# motor_board_tmc.net
KiCad netlist of a schematic drawn in EAGLE
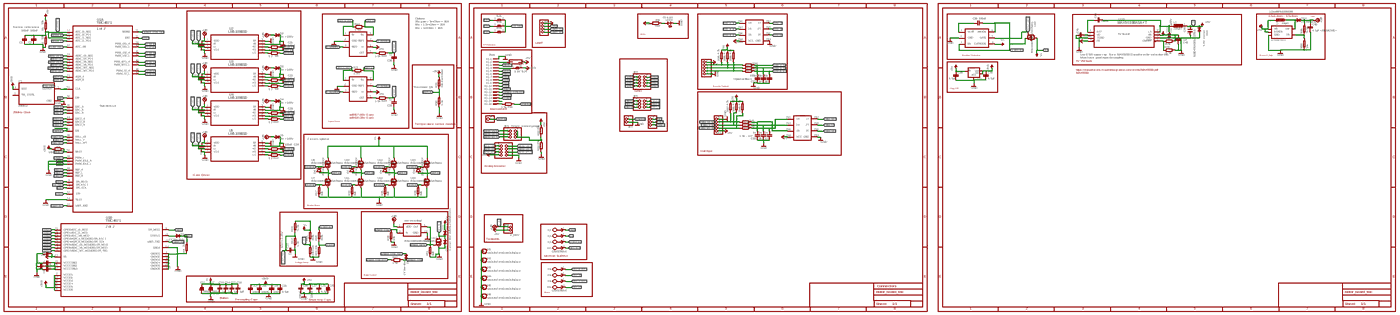
[diagram p0: schematic, sheet 1, overview]
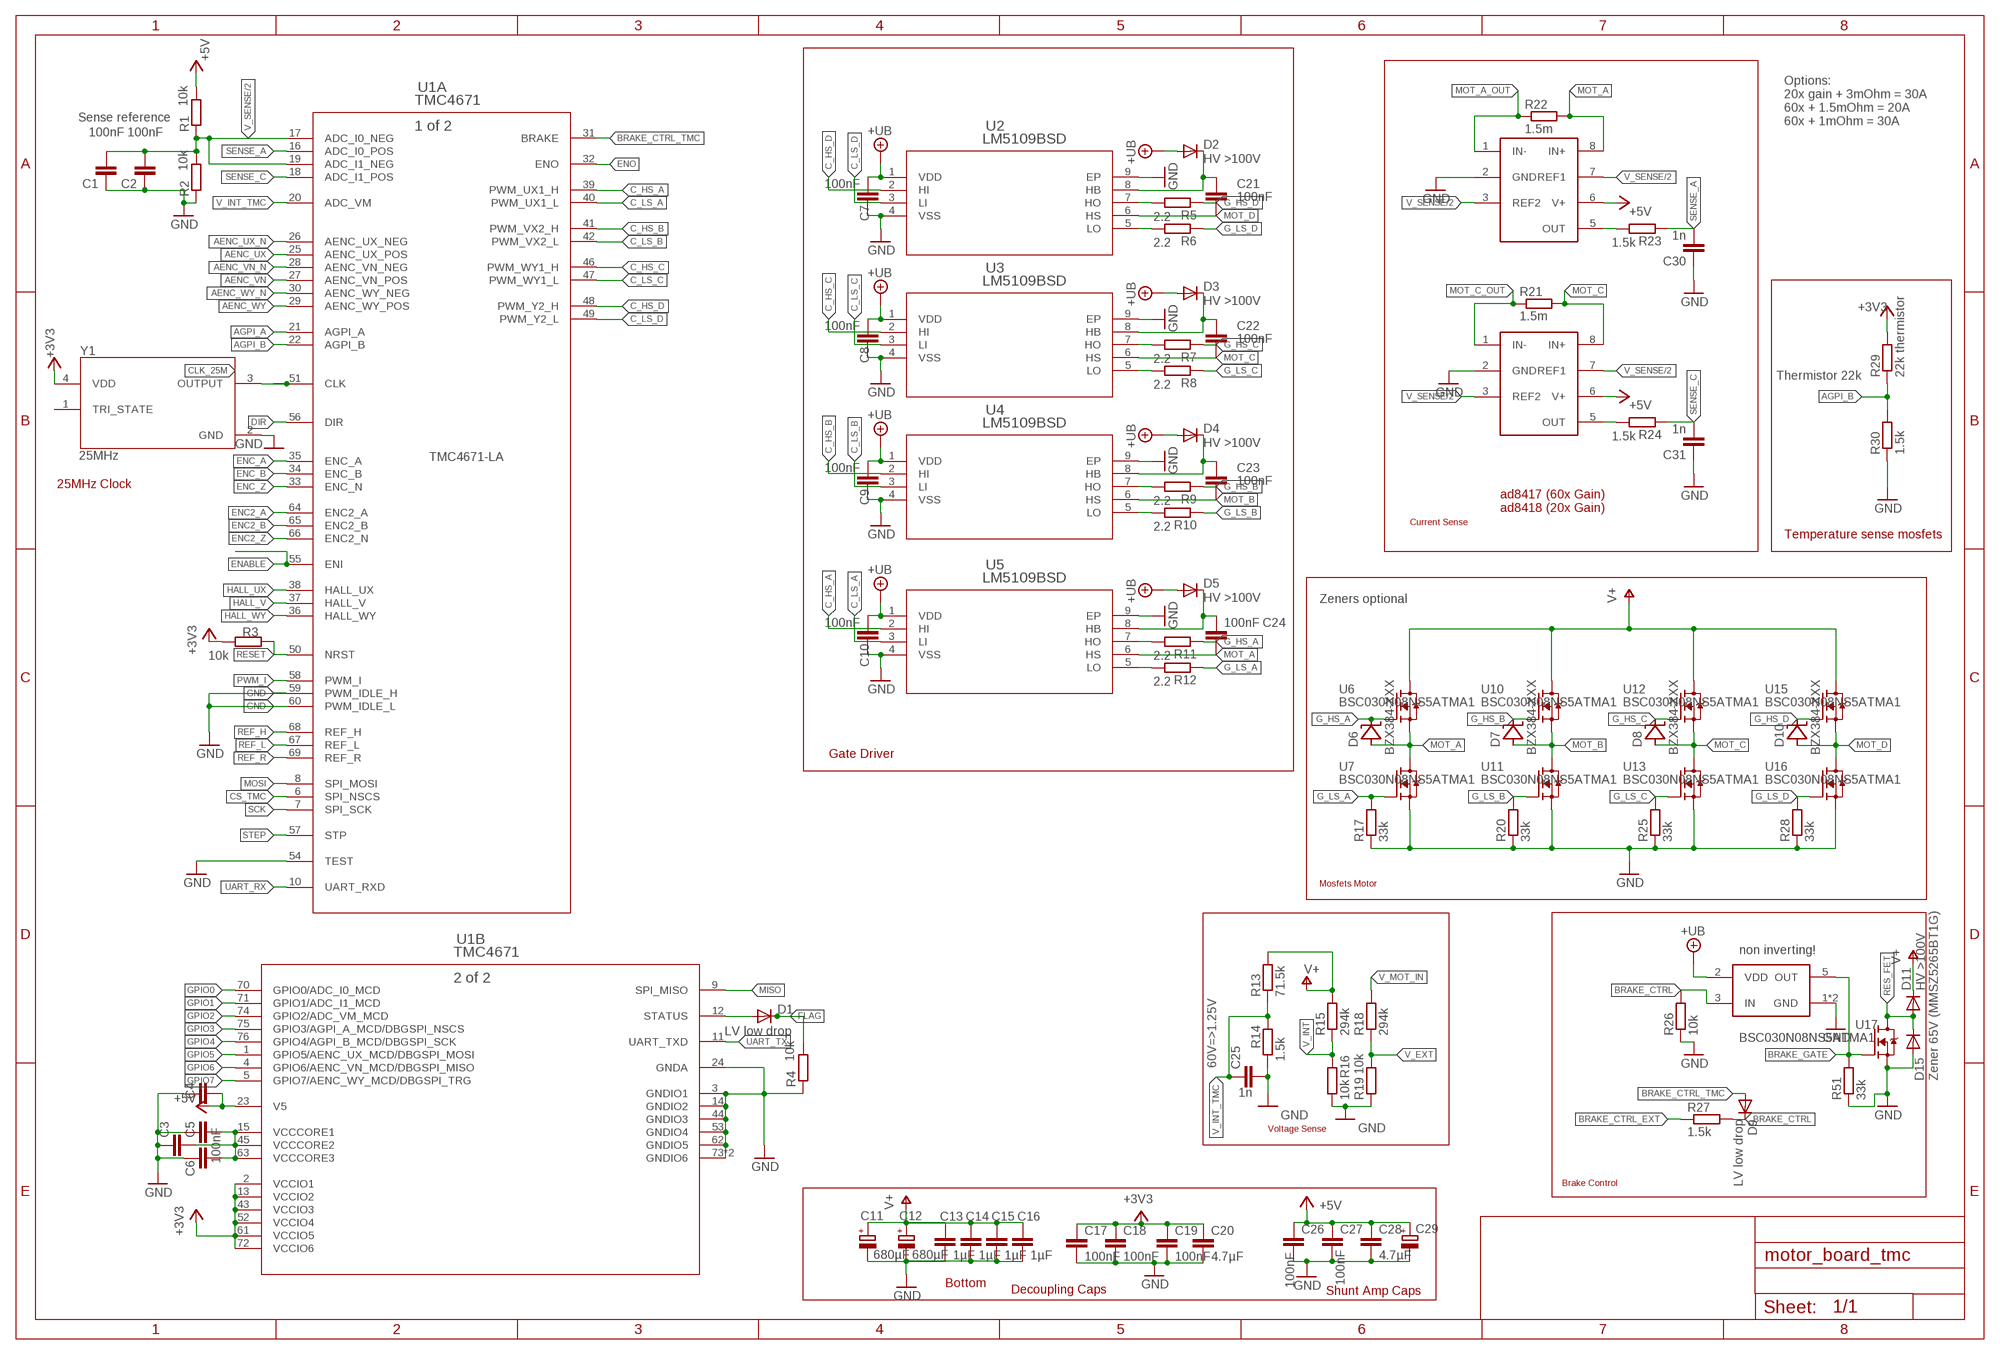
[diagram p1: schematic, sheet 1, part 1 of 4]
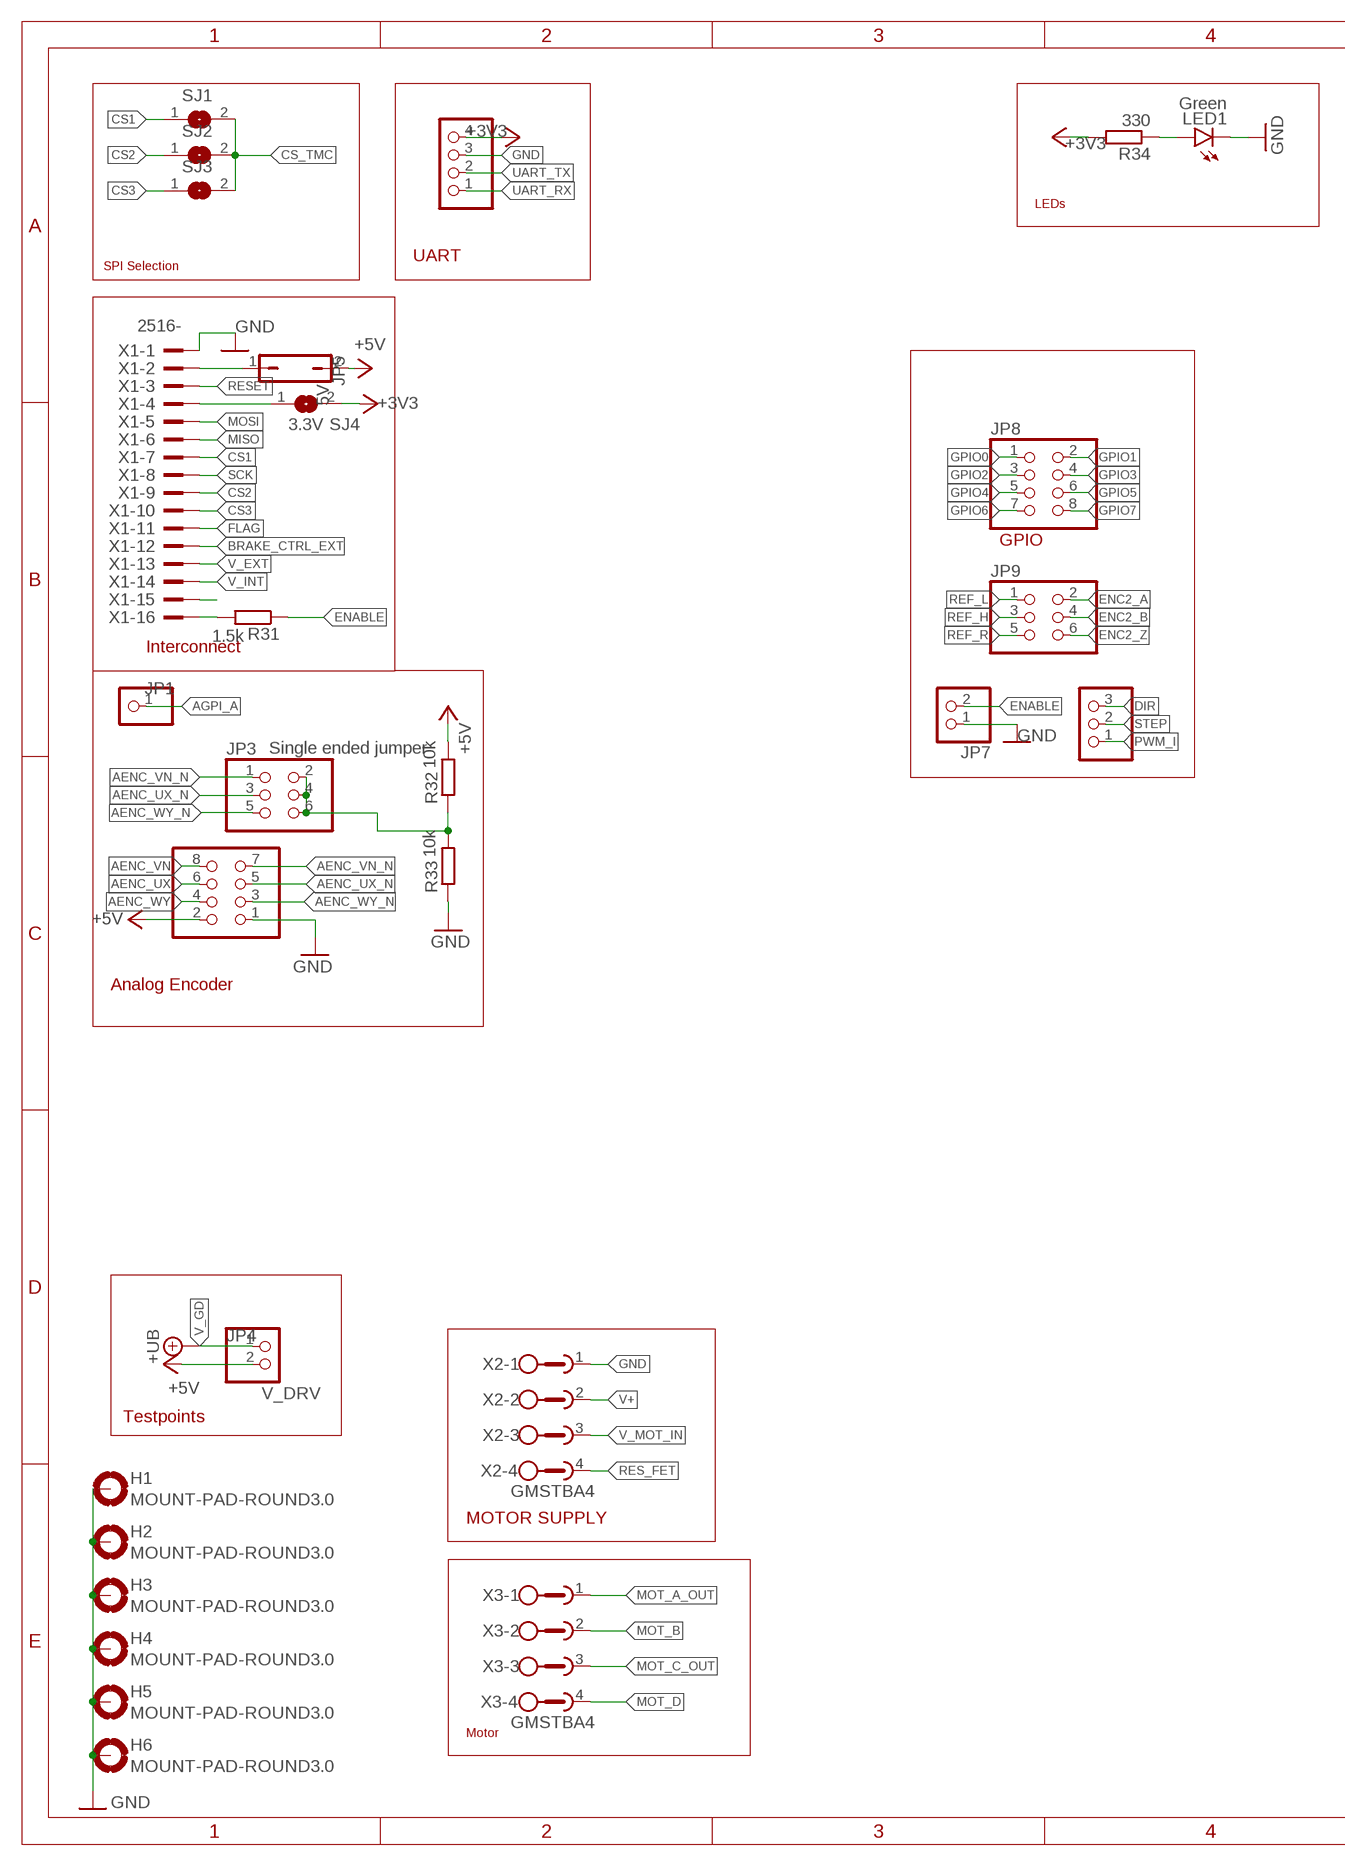
[diagram p2: schematic, sheet 1, part 2 of 4]
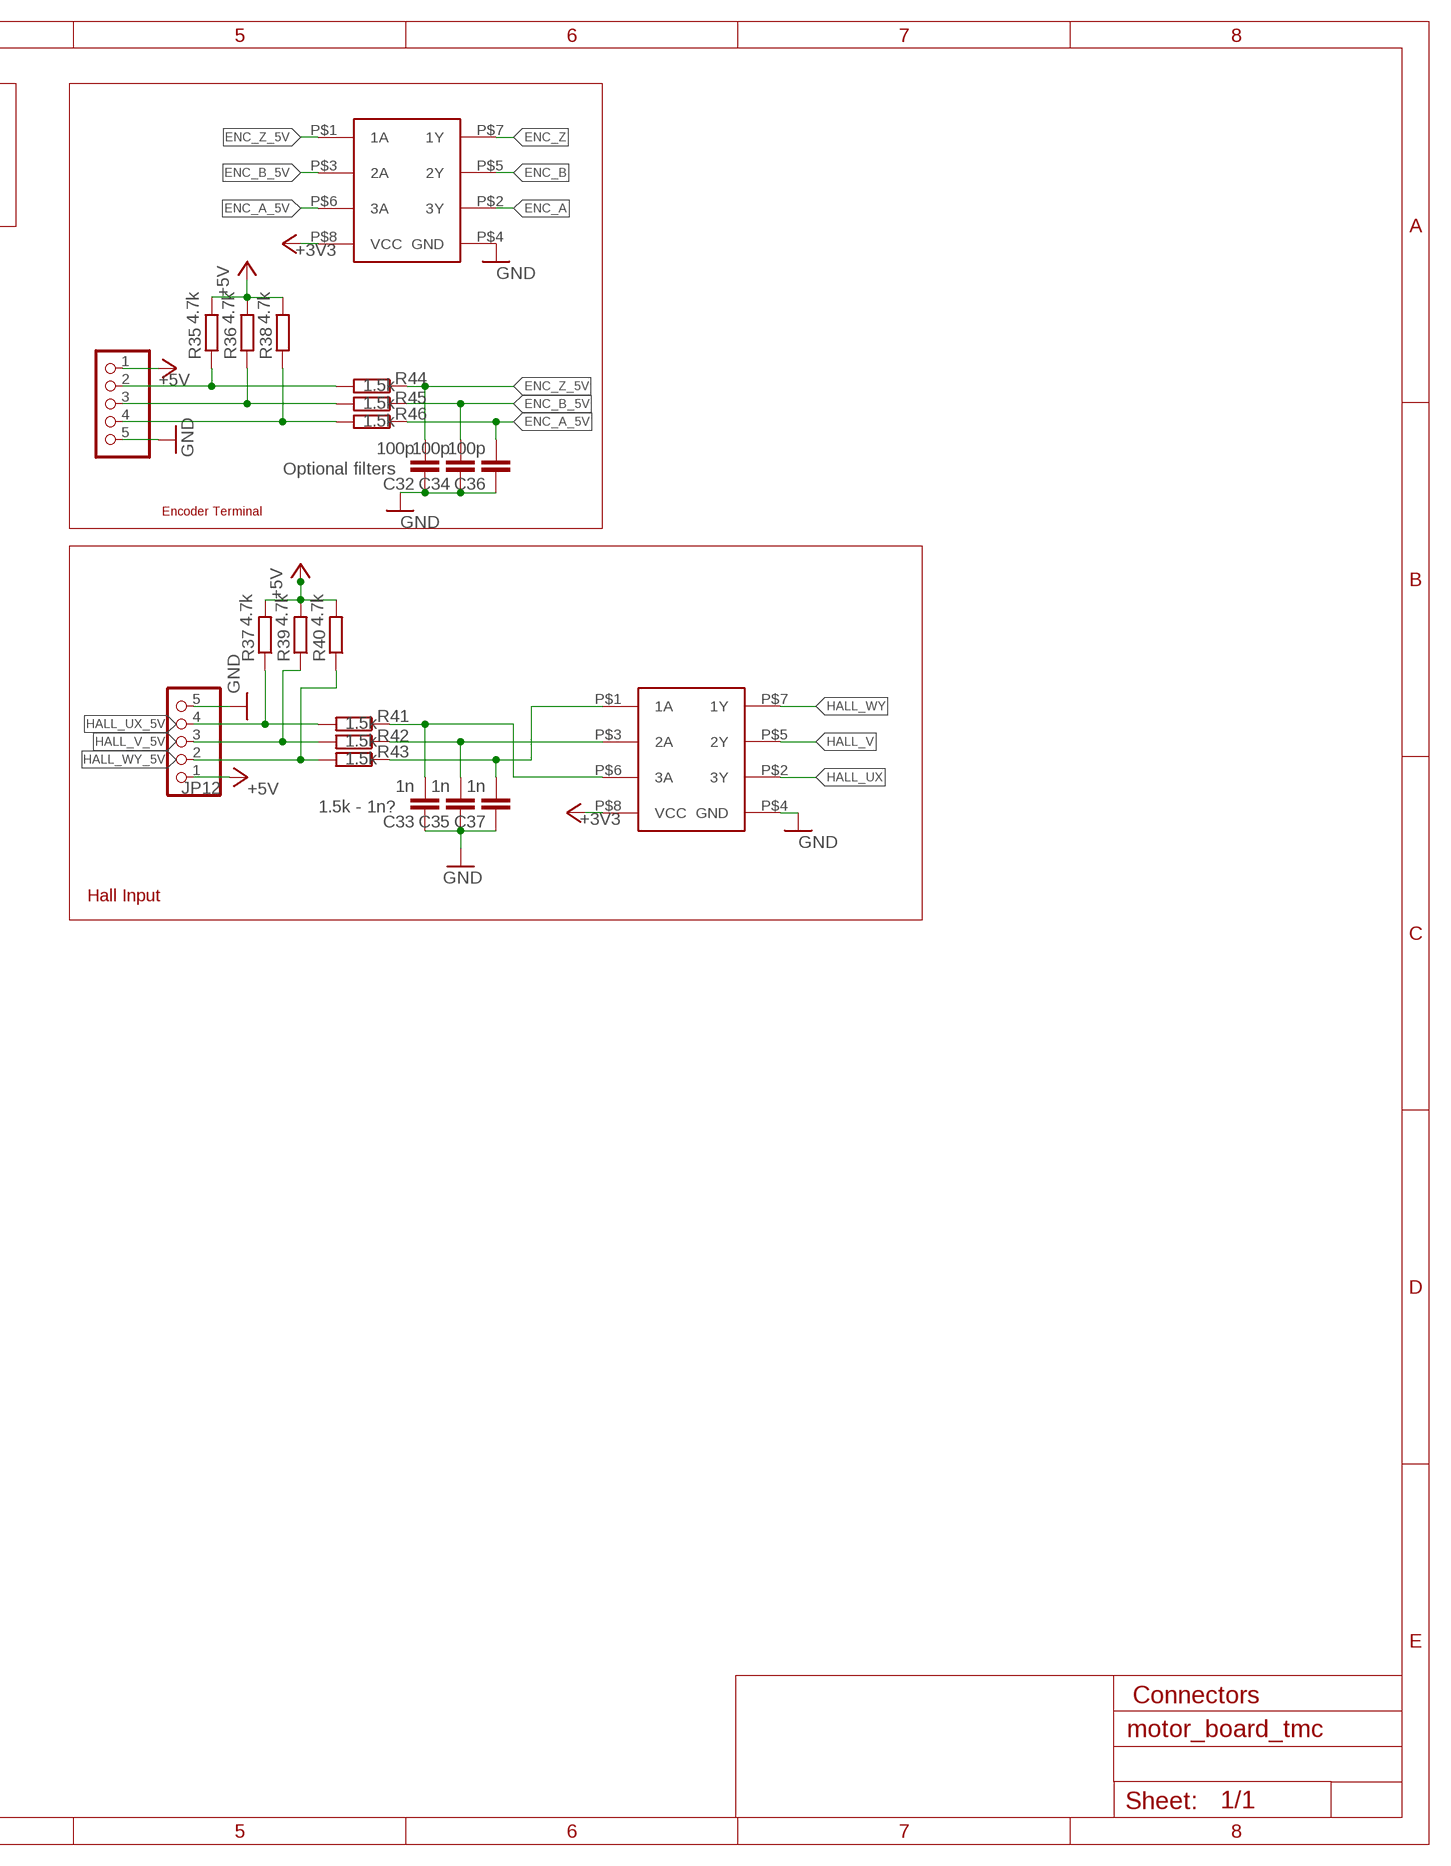
[diagram p3: schematic, sheet 1, part 3 of 4]
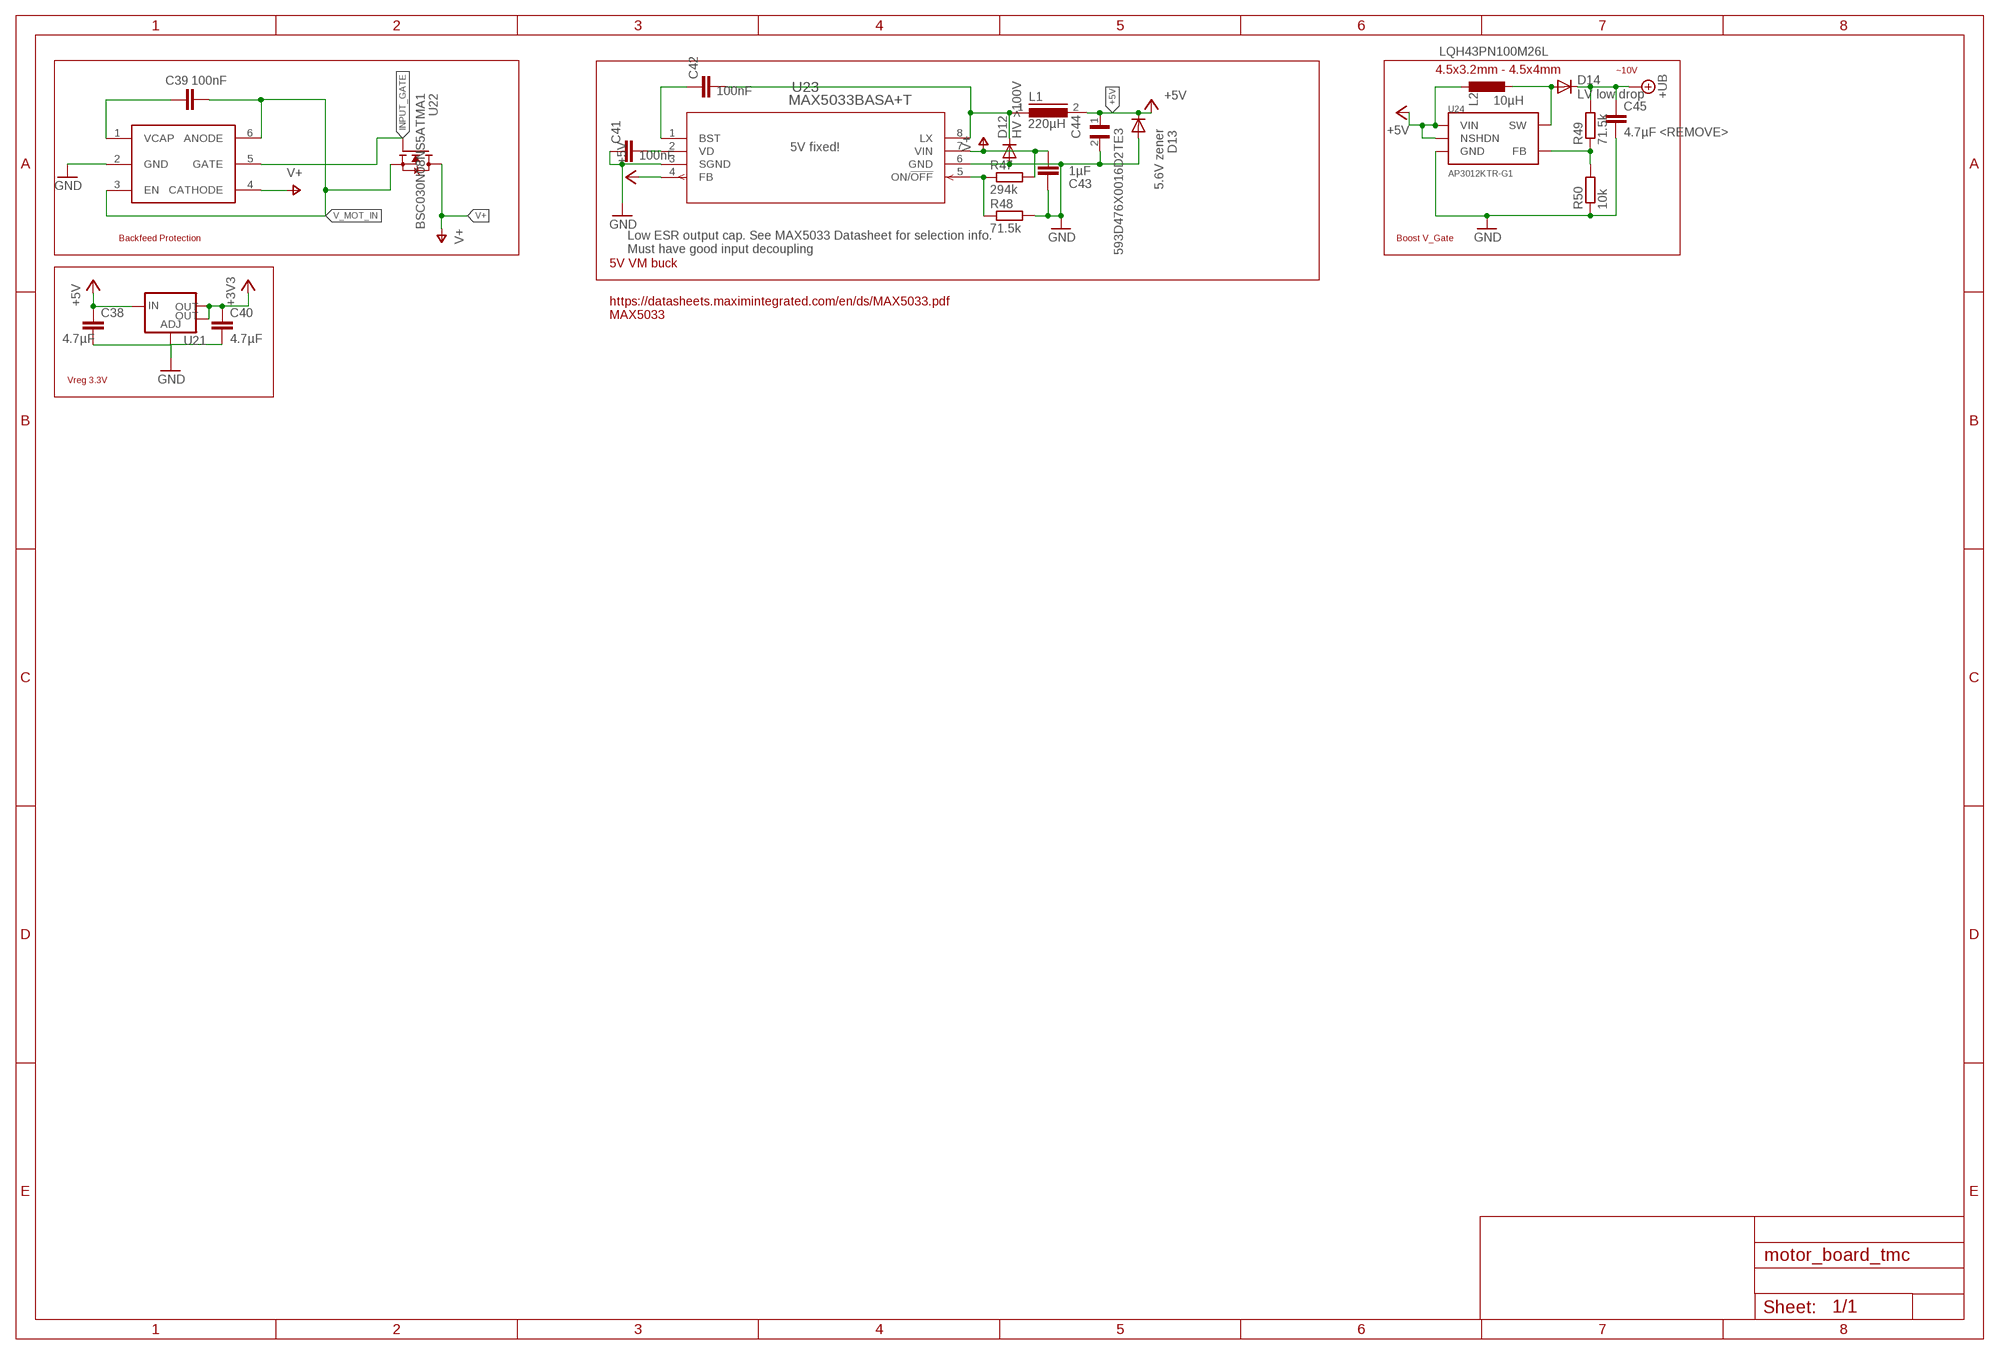
[diagram p4: schematic, sheet 1, part 4 of 4]

(export (version "E")
  (design (tool "Eeschema 10.0.6"))
  (components
    (comp (ref "C1")
      (value "100nF")
      (footprint "eagle-import:C0603")
      (libsource (lib "eagle-import") (part "C-EUC0603"))
    )
    (comp (ref "C2")
      (value "100nF")
      (footprint "eagle-import:C0603")
      (libsource (lib "eagle-import") (part "C-EUC0603"))
    )
    (comp (ref "C3")
      (value "100nF")
      (footprint "eagle-import:C0603")
      (libsource (lib "eagle-import") (part "C-EUC0603"))
    )
    (comp (ref "C4")
      (value "100nF")
      (footprint "eagle-import:C0603")
      (libsource (lib "eagle-import") (part "C-EUC0603"))
    )
    (comp (ref "C5")
      (value "100nF")
      (footprint "eagle-import:C0603")
      (libsource (lib "eagle-import") (part "C-EUC0603"))
    )
    (comp (ref "C6")
      (value "100nF")
      (footprint "eagle-import:C0603")
      (libsource (lib "eagle-import") (part "C-EUC0603"))
    )
    (comp (ref "C7")
      (value "100nF")
      (footprint "eagle-import:C0603")
      (libsource (lib "eagle-import") (part "C-EUC0603"))
    )
    (comp (ref "C8")
      (value "100nF")
      (footprint "eagle-import:C0603")
      (libsource (lib "eagle-import") (part "C-EUC0603"))
    )
    (comp (ref "C9")
      (value "100nF")
      (footprint "eagle-import:C0603")
      (libsource (lib "eagle-import") (part "C-EUC0603"))
    )
    (comp (ref "C10")
      (value "100nF")
      (footprint "eagle-import:C0603")
      (libsource (lib "eagle-import") (part "C-EUC0603"))
    )
    (comp (ref "C11")
      (value "680µF")
      (footprint "eagle-import:E7,5-16")
      (libsource (lib "eagle-import") (part "CPOL-EUE7.5-16"))
    )
    (comp (ref "C12")
      (value "680µF")
      (footprint "eagle-import:E7,5-16")
      (libsource (lib "eagle-import") (part "CPOL-EUE7.5-16"))
    )
    (comp (ref "C13")
      (value "1µF")
      (footprint "eagle-import:C1206")
      (libsource (lib "eagle-import") (part "C-EUC1206"))
    )
    (comp (ref "C14")
      (value "1µF")
      (footprint "eagle-import:C1206")
      (libsource (lib "eagle-import") (part "C-EUC1206"))
    )
    (comp (ref "C15")
      (value "1µF")
      (footprint "eagle-import:C1206")
      (libsource (lib "eagle-import") (part "C-EUC1206"))
    )
    (comp (ref "C16")
      (value "1µF")
      (footprint "eagle-import:C1206")
      (libsource (lib "eagle-import") (part "C-EUC1206"))
    )
    (comp (ref "C17")
      (value "100nF")
      (footprint "eagle-import:C0603")
      (libsource (lib "eagle-import") (part "C-EUC0603"))
    )
    (comp (ref "C18")
      (value "100nF")
      (footprint "eagle-import:C0603")
      (libsource (lib "eagle-import") (part "C-EUC0603"))
    )
    (comp (ref "C19")
      (value "100nF")
      (footprint "eagle-import:C0603")
      (libsource (lib "eagle-import") (part "C-EUC0603"))
    )
    (comp (ref "C20")
      (value "4.7µF")
      (footprint "eagle-import:C0805")
      (libsource (lib "eagle-import") (part "C-EUC0805"))
    )
    (comp (ref "C21")
      (value "100nF")
      (footprint "eagle-import:C0805")
      (libsource (lib "eagle-import") (part "C-EUC0805"))
    )
    (comp (ref "C22")
      (value "100nF")
      (footprint "eagle-import:C0805")
      (libsource (lib "eagle-import") (part "C-EUC0805"))
    )
    (comp (ref "C23")
      (value "100nF")
      (footprint "eagle-import:C0805")
      (libsource (lib "eagle-import") (part "C-EUC0805"))
    )
    (comp (ref "C24")
      (value "100nF")
      (footprint "eagle-import:C0805")
      (libsource (lib "eagle-import") (part "C-EUC0805"))
    )
    (comp (ref "C25")
      (value "1n")
      (footprint "eagle-import:C0603")
      (libsource (lib "eagle-import") (part "C-EUC0603"))
    )
    (comp (ref "C26")
      (value "100nF")
      (footprint "eagle-import:C0603")
      (libsource (lib "eagle-import") (part "C-EUC0603"))
    )
    (comp (ref "C27")
      (value "100nF")
      (footprint "eagle-import:C0603")
      (libsource (lib "eagle-import") (part "C-EUC0603"))
    )
    (comp (ref "C28")
      (value "4.7µF")
      (footprint "eagle-import:C0805")
      (libsource (lib "eagle-import") (part "C-EUC0805"))
    )
    (comp (ref "C29")
      (value "CPOL-EUE5-8.5")
      (footprint "eagle-import:E5-8,5")
      (libsource (lib "eagle-import") (part "CPOL-EUE5-8.5"))
    )
    (comp (ref "C30")
      (value "1n")
      (footprint "eagle-import:C0603")
      (libsource (lib "eagle-import") (part "C-EUC0603"))
    )
    (comp (ref "C31")
      (value "1n")
      (footprint "eagle-import:C0603")
      (libsource (lib "eagle-import") (part "C-EUC0603"))
    )
    (comp (ref "C32")
      (value "100p")
      (footprint "eagle-import:C0603")
      (libsource (lib "eagle-import") (part "C-EUC0603"))
    )
    (comp (ref "C33")
      (value "1n")
      (footprint "eagle-import:C0603")
      (libsource (lib "eagle-import") (part "C-EUC0603"))
    )
    (comp (ref "C34")
      (value "100p")
      (footprint "eagle-import:C0603")
      (libsource (lib "eagle-import") (part "C-EUC0603"))
    )
    (comp (ref "C35")
      (value "1n")
      (footprint "eagle-import:C0603")
      (libsource (lib "eagle-import") (part "C-EUC0603"))
    )
    (comp (ref "C36")
      (value "100p")
      (footprint "eagle-import:C0603")
      (libsource (lib "eagle-import") (part "C-EUC0603"))
    )
    (comp (ref "C37")
      (value "1n")
      (footprint "eagle-import:C0603")
      (libsource (lib "eagle-import") (part "C-EUC0603"))
    )
    (comp (ref "C38")
      (value "4.7µF")
      (footprint "eagle-import:C0805")
      (libsource (lib "eagle-import") (part "C-EUC0805"))
    )
    (comp (ref "C39")
      (value "100nF")
      (footprint "eagle-import:C0805")
      (libsource (lib "eagle-import") (part "C-EUC0805"))
    )
    (comp (ref "C40")
      (value "4.7µF")
      (footprint "eagle-import:C0805")
      (libsource (lib "eagle-import") (part "C-EUC0805"))
    )
    (comp (ref "C41")
      (value "100nF")
      (footprint "eagle-import:C0603")
      (libsource (lib "eagle-import") (part "C-EUC0603"))
    )
    (comp (ref "C42")
      (value "100nF")
      (footprint "eagle-import:C0603")
      (libsource (lib "eagle-import") (part "C-EUC0603"))
    )
    (comp (ref "C43")
      (value "1µF")
      (footprint "eagle-import:C1206")
      (libsource (lib "eagle-import") (part "C-EUC1206"))
    )
    (comp (ref "C44")
      (value "593D476X0016D2TE3")
      (footprint "eagle-import:CAPPM7343X310N")
      (fields (field (name "DIGI-KEY_PART_NUMBER") "718-2142-1-ND") (field (name "MF") "Vishay Sprague"))
      (libsource (lib "eagle-import") (part "593D476X0016D2TE3"))
    )
    (comp (ref "C45")
      (value "4.7µF <REMOVE>")
      (footprint "eagle-import:C0805")
      (libsource (lib "eagle-import") (part "C-EUC0805"))
    )
    (comp (ref "D1")
      (value "LV low drop")
      (footprint "eagle-import:SOD-123FL")
      (libsource (lib "eagle-import") (part "DIODE_SOD-123FL"))
    )
    (comp (ref "D2")
      (value "HV >100V")
      (footprint "eagle-import:SOD-123FL")
      (libsource (lib "eagle-import") (part "DIODE_SOD-123FL"))
    )
    (comp (ref "D3")
      (value "HV >100V")
      (footprint "eagle-import:SOD-123FL")
      (libsource (lib "eagle-import") (part "DIODE_SOD-123FL"))
    )
    (comp (ref "D4")
      (value "HV >100V")
      (footprint "eagle-import:SOD-123FL")
      (libsource (lib "eagle-import") (part "DIODE_SOD-123FL"))
    )
    (comp (ref "D5")
      (value "HV >100V")
      (footprint "eagle-import:SOD-123FL")
      (libsource (lib "eagle-import") (part "DIODE_SOD-123FL"))
    )
    (comp (ref "D6")
      (value "BZX384-XXX")
      (footprint "eagle-import:SOD323-R")
      (libsource (lib "eagle-import") (part "BZX384-XXX"))
    )
    (comp (ref "D7")
      (value "BZX384-XXX")
      (footprint "eagle-import:SOD323-R")
      (libsource (lib "eagle-import") (part "BZX384-XXX"))
    )
    (comp (ref "D8")
      (value "BZX384-XXX")
      (footprint "eagle-import:SOD323-R")
      (libsource (lib "eagle-import") (part "BZX384-XXX"))
    )
    (comp (ref "D9")
      (value "LV low drop")
      (footprint "eagle-import:SOD-123FL")
      (libsource (lib "eagle-import") (part "DIODE_SOD-123FL"))
    )
    (comp (ref "D10")
      (value "BZX384-XXX")
      (footprint "eagle-import:SOD323-R")
      (libsource (lib "eagle-import") (part "BZX384-XXX"))
    )
    (comp (ref "D11")
      (value "HV >100V")
      (footprint "eagle-import:SOD-123FL")
      (libsource (lib "eagle-import") (part "DIODE_SOD-123FL"))
    )
    (comp (ref "D12")
      (value "HV >100V")
      (footprint "eagle-import:SOD-123FL")
      (libsource (lib "eagle-import") (part "DIODE_SOD-123FL"))
    )
    (comp (ref "D13")
      (value "5.6V zener")
      (footprint "eagle-import:SOD-123FL")
      (libsource (lib "eagle-import") (part "DIODE_SOD-123FL"))
    )
    (comp (ref "D14")
      (value "LV low drop")
      (footprint "eagle-import:SOD-123FL")
      (libsource (lib "eagle-import") (part "DIODE_SOD-123FL"))
    )
    (comp (ref "D15")
      (value "Zener 65V (MMSZ5265BT1G)")
      (footprint "eagle-import:SOD-123FL")
      (libsource (lib "eagle-import") (part "DIODE_SOD-123FL"))
    )
    (comp (ref "H1")
      (value "MOUNT-PAD-ROUND3.0")
      (footprint "eagle-import:3,0-PAD")
      (libsource (lib "eagle-import") (part "MOUNT-PAD-ROUND3.0"))
    )
    (comp (ref "H2")
      (value "MOUNT-PAD-ROUND3.0")
      (footprint "eagle-import:3,0-PAD")
      (libsource (lib "eagle-import") (part "MOUNT-PAD-ROUND3.0"))
    )
    (comp (ref "H3")
      (value "MOUNT-PAD-ROUND3.0")
      (footprint "eagle-import:3,0-PAD")
      (libsource (lib "eagle-import") (part "MOUNT-PAD-ROUND3.0"))
    )
    (comp (ref "H4")
      (value "MOUNT-PAD-ROUND3.0")
      (footprint "eagle-import:3,0-PAD")
      (libsource (lib "eagle-import") (part "MOUNT-PAD-ROUND3.0"))
    )
    (comp (ref "H5")
      (value "MOUNT-PAD-ROUND3.0")
      (footprint "eagle-import:3,0-PAD")
      (libsource (lib "eagle-import") (part "MOUNT-PAD-ROUND3.0"))
    )
    (comp (ref "H6")
      (value "MOUNT-PAD-ROUND3.0")
      (footprint "eagle-import:3,0-PAD")
      (libsource (lib "eagle-import") (part "MOUNT-PAD-ROUND3.0"))
    )
    (comp (ref "JP1")
      (value "PINHD-1X1")
      (footprint "eagle-import:1X01")
      (libsource (lib "eagle-import") (part "PINHD-1X1"))
    )
    (comp (ref "JP2")
      (value "PINHD-2X4")
      (footprint "eagle-import:2X04")
      (libsource (lib "eagle-import") (part "PINHD-2X4"))
    )
    (comp (ref "JP3")
      (value "PINHD-2X3")
      (footprint "eagle-import:2X03")
      (libsource (lib "eagle-import") (part "PINHD-2X3"))
    )
    (comp (ref "JP4")
      (value "V_DRV")
      (footprint "eagle-import:1X02")
      (libsource (lib "eagle-import") (part "PINHD-1X2"))
    )
    (comp (ref "JP5")
      (value "5V")
      (footprint "eagle-import:JP1")
      (libsource (lib "eagle-import") (part "JP1Q"))
    )
    (comp (ref "JP6")
      (value "PINHD-1X4")
      (footprint "eagle-import:1X04")
      (libsource (lib "eagle-import") (part "PINHD-1X4"))
    )
    (comp (ref "JP7")
      (value "PINHD-1X2")
      (footprint "eagle-import:1X02")
      (libsource (lib "eagle-import") (part "PINHD-1X2"))
    )
    (comp (ref "JP8")
      (value "PINHD-2X4")
      (footprint "eagle-import:2X04")
      (libsource (lib "eagle-import") (part "PINHD-2X4"))
    )
    (comp (ref "JP9")
      (value "PINHD-2X3")
      (footprint "eagle-import:2X03")
      (libsource (lib "eagle-import") (part "PINHD-2X3"))
    )
    (comp (ref "JP10")
      (value "PINHD-1X3")
      (footprint "eagle-import:1X03")
      (libsource (lib "eagle-import") (part "PINHD-1X3"))
    )
    (comp (ref "JP11")
      (value "PINHD-1X5")
      (footprint "eagle-import:1X05")
      (libsource (lib "eagle-import") (part "PINHD-1X5"))
    )
    (comp (ref "JP12")
      (value "PINHD-1X5")
      (footprint "eagle-import:1X05")
      (libsource (lib "eagle-import") (part "PINHD-1X5"))
    )
    (comp (ref "L1")
      (value "220µH")
      (footprint "eagle-import:8MMINDUCTOR")
      (libsource (lib "eagle-import") (part "8MMINDUCTOR"))
    )
    (comp (ref "L2")
      (value "10µH")
      (footprint "eagle-import:L4532P")
      (libsource (lib "eagle-import") (part "L-EUL4532P"))
    )
    (comp (ref "LED1")
      (value "Green")
      (footprint "eagle-import:SML0805")
      (libsource (lib "eagle-import") (part "LEDSML0805"))
    )
    (comp (ref "R1")
      (value "10k")
      (footprint "eagle-import:R0603")
      (libsource (lib "eagle-import") (part "R-EU_R0603"))
    )
    (comp (ref "R2")
      (value "10k")
      (footprint "eagle-import:R0603")
      (libsource (lib "eagle-import") (part "R-EU_R0603"))
    )
    (comp (ref "R3")
      (value "10k")
      (footprint "eagle-import:R0603")
      (libsource (lib "eagle-import") (part "R-EU_R0603"))
    )
    (comp (ref "R4")
      (value "10k")
      (footprint "eagle-import:R0603")
      (libsource (lib "eagle-import") (part "R-EU_R0603"))
    )
    (comp (ref "R5")
      (value "2.2")
      (footprint "eagle-import:R0603")
      (libsource (lib "eagle-import") (part "R-EU_R0603"))
    )
    (comp (ref "R6")
      (value "2.2")
      (footprint "eagle-import:R0603")
      (libsource (lib "eagle-import") (part "R-EU_R0603"))
    )
    (comp (ref "R7")
      (value "2.2")
      (footprint "eagle-import:R0603")
      (libsource (lib "eagle-import") (part "R-EU_R0603"))
    )
    (comp (ref "R8")
      (value "2.2")
      (footprint "eagle-import:R0603")
      (libsource (lib "eagle-import") (part "R-EU_R0603"))
    )
    (comp (ref "R9")
      (value "2.2")
      (footprint "eagle-import:R0603")
      (libsource (lib "eagle-import") (part "R-EU_R0603"))
    )
    (comp (ref "R10")
      (value "2.2")
      (footprint "eagle-import:R0603")
      (libsource (lib "eagle-import") (part "R-EU_R0603"))
    )
    (comp (ref "R11")
      (value "2.2")
      (footprint "eagle-import:R0603")
      (libsource (lib "eagle-import") (part "R-EU_R0603"))
    )
    (comp (ref "R12")
      (value "2.2")
      (footprint "eagle-import:R0603")
      (libsource (lib "eagle-import") (part "R-EU_R0603"))
    )
    (comp (ref "R13")
      (value "71.5k")
      (footprint "eagle-import:R0805")
      (libsource (lib "eagle-import") (part "R-EU_R0805"))
    )
    (comp (ref "R14")
      (value "1.5k")
      (footprint "eagle-import:R0603")
      (libsource (lib "eagle-import") (part "R-EU_R0603"))
    )
    (comp (ref "R15")
      (value "294k")
      (footprint "eagle-import:R0805")
      (libsource (lib "eagle-import") (part "R-EU_R0805"))
    )
    (comp (ref "R16")
      (value "10k")
      (footprint "eagle-import:R0603")
      (libsource (lib "eagle-import") (part "R-EU_R0603"))
    )
    (comp (ref "R17")
      (value "33k")
      (footprint "eagle-import:R0603")
      (libsource (lib "eagle-import") (part "R-EU_R0603"))
    )
    (comp (ref "R18")
      (value "294k")
      (footprint "eagle-import:R0805")
      (libsource (lib "eagle-import") (part "R-EU_R0805"))
    )
    (comp (ref "R19")
      (value "10k")
      (footprint "eagle-import:R0603")
      (libsource (lib "eagle-import") (part "R-EU_R0603"))
    )
    (comp (ref "R20")
      (value "33k")
      (footprint "eagle-import:R0603")
      (libsource (lib "eagle-import") (part "R-EU_R0603"))
    )
    (comp (ref "R21")
      (value "1.5m")
      (footprint "eagle-import:R2512")
      (libsource (lib "eagle-import") (part "R-EU_R2512"))
    )
    (comp (ref "R22")
      (value "1.5m")
      (footprint "eagle-import:R2512")
      (libsource (lib "eagle-import") (part "R-EU_R2512"))
    )
    (comp (ref "R23")
      (value "1.5k")
      (footprint "eagle-import:R0603")
      (libsource (lib "eagle-import") (part "R-EU_R0603"))
    )
    (comp (ref "R24")
      (value "1.5k")
      (footprint "eagle-import:R0603")
      (libsource (lib "eagle-import") (part "R-EU_R0603"))
    )
    (comp (ref "R25")
      (value "33k")
      (footprint "eagle-import:R0603")
      (libsource (lib "eagle-import") (part "R-EU_R0603"))
    )
    (comp (ref "R26")
      (value "10k")
      (footprint "eagle-import:R0603")
      (libsource (lib "eagle-import") (part "R-EU_R0603"))
    )
    (comp (ref "R27")
      (value "1.5k")
      (footprint "eagle-import:R0603")
      (libsource (lib "eagle-import") (part "R-EU_R0603"))
    )
    (comp (ref "R28")
      (value "33k")
      (footprint "eagle-import:R0603")
      (libsource (lib "eagle-import") (part "R-EU_R0603"))
    )
    (comp (ref "R29")
      (value "22k thermistor")
      (footprint "eagle-import:R0603")
      (libsource (lib "eagle-import") (part "R-EU_R0603"))
    )
    (comp (ref "R30")
      (value "1.5k")
      (footprint "eagle-import:R0603")
      (libsource (lib "eagle-import") (part "R-EU_R0603"))
    )
    (comp (ref "R31")
      (value "1.5k")
      (footprint "eagle-import:R0603")
      (libsource (lib "eagle-import") (part "R-EU_R0603"))
    )
    (comp (ref "R32")
      (value "10k")
      (footprint "eagle-import:R0603")
      (libsource (lib "eagle-import") (part "R-EU_R0603"))
    )
    (comp (ref "R33")
      (value "10k")
      (footprint "eagle-import:R0603")
      (libsource (lib "eagle-import") (part "R-EU_R0603"))
    )
    (comp (ref "R34")
      (value "330")
      (footprint "eagle-import:R0603")
      (libsource (lib "eagle-import") (part "R-EU_R0603"))
    )
    (comp (ref "R35")
      (value "4.7k")
      (footprint "eagle-import:R0603")
      (libsource (lib "eagle-import") (part "R-EU_R0603"))
    )
    (comp (ref "R36")
      (value "4.7k")
      (footprint "eagle-import:R0603")
      (libsource (lib "eagle-import") (part "R-EU_R0603"))
    )
    (comp (ref "R37")
      (value "4.7k")
      (footprint "eagle-import:R0603")
      (libsource (lib "eagle-import") (part "R-EU_R0603"))
    )
    (comp (ref "R38")
      (value "4.7k")
      (footprint "eagle-import:R0603")
      (libsource (lib "eagle-import") (part "R-EU_R0603"))
    )
    (comp (ref "R39")
      (value "4.7k")
      (footprint "eagle-import:R0603")
      (libsource (lib "eagle-import") (part "R-EU_R0603"))
    )
    (comp (ref "R40")
      (value "4.7k")
      (footprint "eagle-import:R0603")
      (libsource (lib "eagle-import") (part "R-EU_R0603"))
    )
    (comp (ref "R41")
      (value "1.5k")
      (footprint "eagle-import:R0603")
      (libsource (lib "eagle-import") (part "R-EU_R0603"))
    )
    (comp (ref "R42")
      (value "1.5k")
      (footprint "eagle-import:R0603")
      (libsource (lib "eagle-import") (part "R-EU_R0603"))
    )
    (comp (ref "R43")
      (value "1.5k")
      (footprint "eagle-import:R0603")
      (libsource (lib "eagle-import") (part "R-EU_R0603"))
    )
    (comp (ref "R44")
      (value "1.5k")
      (footprint "eagle-import:R0603")
      (libsource (lib "eagle-import") (part "R-EU_R0603"))
    )
    (comp (ref "R45")
      (value "1.5k")
      (footprint "eagle-import:R0603")
      (libsource (lib "eagle-import") (part "R-EU_R0603"))
    )
    (comp (ref "R46")
      (value "1.5k")
      (footprint "eagle-import:R0603")
      (libsource (lib "eagle-import") (part "R-EU_R0603"))
    )
    (comp (ref "R47")
      (value "294k")
      (footprint "eagle-import:R0805")
      (libsource (lib "eagle-import") (part "R-EU_R0805"))
    )
    (comp (ref "R48")
      (value "71.5k")
      (footprint "eagle-import:R0805")
      (libsource (lib "eagle-import") (part "R-EU_R0805"))
    )
    (comp (ref "R49")
      (value "71.5k")
      (footprint "eagle-import:R0805")
      (libsource (lib "eagle-import") (part "R-EU_R0805"))
    )
    (comp (ref "R50")
      (value "10k")
      (footprint "eagle-import:R0603")
      (libsource (lib "eagle-import") (part "R-EU_R0603"))
    )
    (comp (ref "R51")
      (value "33k")
      (footprint "eagle-import:R0603")
      (libsource (lib "eagle-import") (part "R-EU_R0603"))
    )
    (comp (ref "SJ1") (value "SJ") (footprint "eagle-import:SJ") (libsource (lib "eagle-import") (part "SJ")))
    (comp (ref "SJ2") (value "SJ") (footprint "eagle-import:SJ") (libsource (lib "eagle-import") (part "SJ")))
    (comp (ref "SJ3") (value "SJ") (footprint "eagle-import:SJ") (libsource (lib "eagle-import") (part "SJ")))
    (comp (ref "SJ4")
      (value "3.3V")
      (footprint "eagle-import:SJ")
      (libsource (lib "eagle-import") (part "SJ"))
    )
    (comp (ref "U1")
      (value "TMC4671")
      (footprint "eagle-import:QFN76_10P5X6P5")
      (fields (field (name "MANUFACTURER_PART_NUMBER") "TMC4671ES"))
      (libsource (lib "eagle-import") (part "TMC4671"))
    )
    (comp (ref "U2")
      (value "LM5109BSD")
      (footprint "eagle-import:SDC08A")
      (fields (field (name "MANUFACTURER_PART_NUMBER") "lm5109bsd"))
      (libsource (lib "eagle-import") (part "LM5109BSD"))
    )
    (comp (ref "U3")
      (value "LM5109BSD")
      (footprint "eagle-import:SDC08A")
      (fields (field (name "MANUFACTURER_PART_NUMBER") "lm5109bsd"))
      (libsource (lib "eagle-import") (part "LM5109BSD"))
    )
    (comp (ref "U4")
      (value "LM5109BSD")
      (footprint "eagle-import:SDC08A")
      (fields (field (name "MANUFACTURER_PART_NUMBER") "lm5109bsd"))
      (libsource (lib "eagle-import") (part "LM5109BSD"))
    )
    (comp (ref "U5")
      (value "LM5109BSD")
      (footprint "eagle-import:SDC08A")
      (fields (field (name "MANUFACTURER_PART_NUMBER") "lm5109bsd"))
      (libsource (lib "eagle-import") (part "LM5109BSD"))
    )
    (comp (ref "U6")
      (value "BSC030N08NS5ATMA1")
      (footprint "eagle-import:MOSFET_BSC093N04LSGATMA1")
      (fields (field (name "MF") "Infineon Technologies"))
      (libsource (lib "eagle-import") (part "BSC030N08NS5ATMA1"))
    )
    (comp (ref "U7")
      (value "BSC030N08NS5ATMA1")
      (footprint "eagle-import:MOSFET_BSC093N04LSGATMA1")
      (fields (field (name "MF") "Infineon Technologies"))
      (libsource (lib "eagle-import") (part "BSC030N08NS5ATMA1"))
    )
    (comp (ref "U8")
      (value "AD841X")
      (footprint "eagle-import:MSOP8")
      (libsource (lib "eagle-import") (part "AD841X"))
    )
    (comp (ref "U9")
      (value "AD841X")
      (footprint "eagle-import:MSOP8")
      (libsource (lib "eagle-import") (part "AD841X"))
    )
    (comp (ref "U10")
      (value "BSC030N08NS5ATMA1")
      (footprint "eagle-import:MOSFET_BSC093N04LSGATMA1")
      (fields (field (name "MF") "Infineon Technologies"))
      (libsource (lib "eagle-import") (part "BSC030N08NS5ATMA1"))
    )
    (comp (ref "U11")
      (value "BSC030N08NS5ATMA1")
      (footprint "eagle-import:MOSFET_BSC093N04LSGATMA1")
      (fields (field (name "MF") "Infineon Technologies"))
      (libsource (lib "eagle-import") (part "BSC030N08NS5ATMA1"))
    )
    (comp (ref "U12")
      (value "BSC030N08NS5ATMA1")
      (footprint "eagle-import:MOSFET_BSC093N04LSGATMA1")
      (fields (field (name "MF") "Infineon Technologies"))
      (libsource (lib "eagle-import") (part "BSC030N08NS5ATMA1"))
    )
    (comp (ref "U13")
      (value "BSC030N08NS5ATMA1")
      (footprint "eagle-import:MOSFET_BSC093N04LSGATMA1")
      (fields (field (name "MF") "Infineon Technologies"))
      (libsource (lib "eagle-import") (part "BSC030N08NS5ATMA1"))
    )
    (comp (ref "U14")
      (value "MCP14XX")
      (footprint "eagle-import:SOT23-5L")
      (libsource (lib "eagle-import") (part "MCP14XX"))
    )
    (comp (ref "U15")
      (value "BSC030N08NS5ATMA1")
      (footprint "eagle-import:MOSFET_BSC093N04LSGATMA1")
      (fields (field (name "MF") "Infineon Technologies"))
      (libsource (lib "eagle-import") (part "BSC030N08NS5ATMA1"))
    )
    (comp (ref "U16")
      (value "BSC030N08NS5ATMA1")
      (footprint "eagle-import:MOSFET_BSC093N04LSGATMA1")
      (fields (field (name "MF") "Infineon Technologies"))
      (libsource (lib "eagle-import") (part "BSC030N08NS5ATMA1"))
    )
    (comp (ref "U17")
      (value "BSC030N08NS5ATMA1")
      (footprint "eagle-import:MOSFET_BSC093N04LSGATMA1")
      (fields (field (name "MF") "Infineon Technologies"))
      (libsource (lib "eagle-import") (part "BSC030N08NS5ATMA1"))
    )
    (comp (ref "U18")
      (value "NC7NZ17K8X-3-BUFFER")
      (footprint "eagle-import:VFSOP-8")
      (libsource (lib "eagle-import") (part "NC7NZ17K8X-3-BUFFER"))
    )
    (comp (ref "U19")
      (value "NC7NZ17K8X-3-BUFFER")
      (footprint "eagle-import:VFSOP-8")
      (libsource (lib "eagle-import") (part "NC7NZ17K8X-3-BUFFER"))
    )
    (comp (ref "U20")
      (value "LM74700-Q1")
      (footprint "eagle-import:SOT23-6")
      (libsource (lib "eagle-import") (part "LM74700-Q1"))
    )
    (comp (ref "U21")
      (value "V_REG_LM1117SOT223")
      (footprint "eagle-import:SOT223")
      (libsource (lib "eagle-import") (part "V_REG_LM1117SOT223"))
    )
    (comp (ref "U22")
      (value "BSC030N08NS5ATMA1")
      (footprint "eagle-import:MOSFET_BSC093N04LSGATMA1")
      (fields (field (name "MF") "Infineon Technologies"))
      (libsource (lib "eagle-import") (part "BSC030N08NS5ATMA1"))
    )
    (comp (ref "U23")
      (value "MAX5033BASA+T")
      (footprint "eagle-import:21-0041B_8_MXM")
      (fields (field (name "MANUFACTURER_PART_NUMBER") "max5033basa+T"))
      (libsource (lib "eagle-import") (part "MAX5033BASA+T"))
    )
    (comp (ref "U24")
      (value "AP3012KTR-G1")
      (footprint "eagle-import:SOT23-5L")
      (libsource (lib "eagle-import") (part "AP3012KTR-G1"))
    )
    (comp (ref "X1")
      (value "2516-")
      (footprint "eagle-import:PAK100_2500-16")
      (libsource (lib "eagle-import") (part "2516-"))
    )
    (comp (ref "X2")
      (value "GMSTBA4")
      (footprint "eagle-import:GMSTBA4")
      (fields (field (name "MF") "FARNELL") (field (name "MPN") "1757268"))
      (libsource (lib "eagle-import") (part "GMSTBA4"))
    )
    (comp (ref "X3")
      (value "GMSTBA4")
      (footprint "eagle-import:GMSTBA4")
      (fields (field (name "MF") "FARNELL") (field (name "MPN") "1757268"))
      (libsource (lib "eagle-import") (part "GMSTBA4"))
    )
    (comp (ref "Y1")
      (value "25MHz")
      (footprint "eagle-import:ECS-327KE-TR")
      (fields
        (field (name "DIGIKEY_PART_NUMBER") "XC1751TR-ND")
        (field (name "MANUFACTURER") "ECS Inc.")
        (field (name "MPN") "ECS-327KE-TR")
        (field (name "CREATED_BY") "PCBLayout.com")
      )
      (libsource (lib "eagle-import") (part "ECS-327KE-TR"))
    )
  )
  (nets
    (net (code "1") (name "+3V3") (class "Default")
      (node (ref "C17") (pin "1") (pinfunction "1_1") (pintype "passive"))
      (node (ref "C18") (pin "1") (pinfunction "1_1") (pintype "passive"))
      (node (ref "C19") (pin "1") (pinfunction "1_1") (pintype "passive"))
      (node (ref "C20") (pin "1") (pinfunction "1_1") (pintype "passive"))
      (node (ref "C40") (pin "1") (pinfunction "1_1") (pintype "passive"))
      (node (ref "JP6") (pin "4") (pinfunction "4_4") (pintype "passive"))
      (node (ref "R29") (pin "2") (pinfunction "2_2") (pintype "passive"))
      (node (ref "R3") (pin "2") (pinfunction "2_2") (pintype "passive"))
      (node (ref "R34") (pin "2") (pinfunction "2_2") (pintype "passive"))
      (node (ref "SJ4") (pin "2") (pinfunction "2_2") (pintype "passive"))
      (node (ref "U1") (pin "13") (pinfunction "VCCIO2_13") (pintype "power_in"))
      (node (ref "U1") (pin "2") (pinfunction "VCCIO1_2") (pintype "power_in"))
      (node (ref "U1") (pin "43") (pinfunction "VCCIO3_43") (pintype "power_in"))
      (node (ref "U1") (pin "52") (pinfunction "VCCIO4_52") (pintype "power_in"))
      (node (ref "U1") (pin "61") (pinfunction "VCCIO5_61") (pintype "power_in"))
      (node (ref "U1") (pin "72") (pinfunction "VCCIO6_72") (pintype "power_in"))
      (node (ref "U18") (pin "P$8") (pinfunction "VCC_P$8") (pintype "bidirectional"))
      (node (ref "U19") (pin "P$8") (pinfunction "VCC_P$8") (pintype "bidirectional"))
      (node (ref "U21") (pin "2") (pinfunction "OUT_2") (pintype "output"))
      (node (ref "U21") (pin "4") (pinfunction "OUT_4") (pintype "output"))
      (node (ref "Y1") (pin "4") (pinfunction "VDD_4") (pintype "power_in"))
    )
    (net (code "2") (name "+5V") (class "Default")
      (node (ref "C26") (pin "1") (pinfunction "1_1") (pintype "passive"))
      (node (ref "C27") (pin "1") (pinfunction "1_1") (pintype "passive"))
      (node (ref "C28") (pin "1") (pinfunction "1_1") (pintype "passive"))
      (node (ref "C29") (pin "+") (pinfunction "+_+") (pintype "passive"))
      (node (ref "C38") (pin "1") (pinfunction "1_1") (pintype "passive"))
      (node (ref "C4") (pin "2") (pinfunction "2_2") (pintype "passive"))
      (node (ref "C44") (pin "1") (pinfunction "1_1") (pintype "passive"))
      (node (ref "D13") (pin "C") (pinfunction "C_C") (pintype "passive"))
      (node (ref "JP11") (pin "1") (pinfunction "1_1") (pintype "passive"))
      (node (ref "JP12") (pin "1") (pinfunction "1_1") (pintype "passive"))
      (node (ref "JP2") (pin "2") (pinfunction "2_2") (pintype "passive"))
      (node (ref "JP4") (pin "2") (pinfunction "2_2") (pintype "passive"))
      (node (ref "JP5") (pin "2") (pinfunction "2_2") (pintype "passive"))
      (node (ref "L1") (pin "2") (pinfunction "2_2") (pintype "passive"))
      (node (ref "L2") (pin "1") (pinfunction "1_1") (pintype "passive"))
      (node (ref "R1") (pin "2") (pinfunction "2_2") (pintype "passive"))
      (node (ref "R32") (pin "2") (pinfunction "2_2") (pintype "passive"))
      (node (ref "R35") (pin "2") (pinfunction "2_2") (pintype "passive"))
      (node (ref "R36") (pin "2") (pinfunction "2_2") (pintype "passive"))
      (node (ref "R37") (pin "2") (pinfunction "2_2") (pintype "passive"))
      (node (ref "R38") (pin "2") (pinfunction "2_2") (pintype "passive"))
      (node (ref "R39") (pin "2") (pinfunction "2_2") (pintype "passive"))
      (node (ref "R40") (pin "2") (pinfunction "2_2") (pintype "passive"))
      (node (ref "U1") (pin "23") (pinfunction "V5_23") (pintype "power_in"))
      (node (ref "U21") (pin "3") (pinfunction "IN_3") (pintype "input"))
      (node (ref "U23") (pin "4") (pinfunction "FB_4") (pintype "output"))
      (node (ref "U24") (pin "4") (pinfunction "NSHDN_4") (pintype "bidirectional"))
      (node (ref "U24") (pin "5") (pinfunction "VIN_5") (pintype "bidirectional"))
      (node (ref "U8") (pin "6") (pinfunction "V+_6") (pintype "bidirectional"))
      (node (ref "U9") (pin "6") (pinfunction "V+_6") (pintype "bidirectional"))
    )
    (net (code "3") (name "AENC_UX") (class "Default")
      (node (ref "JP2") (pin "6") (pinfunction "6_6") (pintype "passive"))
      (node (ref "U1") (pin "25") (pinfunction "AENC_UX_POS_25") (pintype "input"))
    )
    (net (code "4") (name "AENC_UX_N") (class "Default")
      (node (ref "JP2") (pin "5") (pinfunction "5_5") (pintype "passive"))
      (node (ref "JP3") (pin "3") (pinfunction "3_3") (pintype "passive"))
      (node (ref "U1") (pin "26") (pinfunction "AENC_UX_NEG_26") (pintype "input"))
    )
    (net (code "5") (name "AENC_VN") (class "Default")
      (node (ref "JP2") (pin "8") (pinfunction "8_8") (pintype "passive"))
      (node (ref "U1") (pin "27") (pinfunction "AENC_VN_POS_27") (pintype "input"))
    )
    (net (code "6") (name "AENC_VN_N") (class "Default")
      (node (ref "JP2") (pin "7") (pinfunction "7_7") (pintype "passive"))
      (node (ref "JP3") (pin "1") (pinfunction "1_1") (pintype "passive"))
      (node (ref "U1") (pin "28") (pinfunction "AENC_VN_NEG_28") (pintype "input"))
    )
    (net (code "7") (name "AENC_WY") (class "Default")
      (node (ref "JP2") (pin "4") (pinfunction "4_4") (pintype "passive"))
      (node (ref "U1") (pin "29") (pinfunction "AENC_WY_POS_29") (pintype "input"))
    )
    (net (code "8") (name "AENC_WY_N") (class "Default")
      (node (ref "JP2") (pin "3") (pinfunction "3_3") (pintype "passive"))
      (node (ref "JP3") (pin "5") (pinfunction "5_5") (pintype "passive"))
      (node (ref "U1") (pin "30") (pinfunction "AENC_WY_NEG_30") (pintype "input"))
    )
    (net (code "9") (name "AGPI_A") (class "Default")
      (node (ref "JP1") (pin "1") (pinfunction "1_1") (pintype "passive"))
      (node (ref "U1") (pin "21") (pinfunction "AGPI_A_21") (pintype "input"))
    )
    (net (code "10") (name "AGPI_B") (class "Default")
      (node (ref "R29") (pin "1") (pinfunction "1_1") (pintype "passive"))
      (node (ref "R30") (pin "2") (pinfunction "2_2") (pintype "passive"))
      (node (ref "U1") (pin "22") (pinfunction "AGPI_B_22") (pintype "input"))
    )
    (net (code "11") (name "BRAKE_CTRL") (class "Default")
      (node (ref "D9") (pin "C") (pinfunction "C_C") (pintype "passive"))
      (node (ref "R26") (pin "2") (pinfunction "2_2") (pintype "passive"))
      (node (ref "R27") (pin "2") (pinfunction "2_2") (pintype "passive"))
      (node (ref "U14") (pin "3") (pinfunction "IN_3") (pintype "bidirectional"))
    )
    (net (code "12") (name "BRAKE_CTRL_EXT") (class "Default")
      (node (ref "R27") (pin "1") (pinfunction "1_1") (pintype "passive"))
      (node (ref "X1") (pin "12") (pinfunction "KL_12") (pintype "passive"))
    )
    (net (code "13") (name "BRAKE_CTRL_TMC") (class "Default")
      (node (ref "D9") (pin "A") (pinfunction "A_A") (pintype "passive"))
      (node (ref "U1") (pin "31") (pinfunction "BRAKE_31") (pintype "output"))
    )
    (net (code "14") (name "BRAKE_GATE") (class "Default")
      (node (ref "R51") (pin "2") (pinfunction "2_2") (pintype "passive"))
      (node (ref "U14") (pin "5") (pinfunction "OUT_5") (pintype "bidirectional"))
      (node (ref "U17") (pin "4") (pinfunction "G_4") (pintype "passive"))
    )
    (net (code "15") (name "CLK_25M") (class "Default")
      (node (ref "U1") (pin "51") (pinfunction "CLK_51") (pintype "input"))
      (node (ref "Y1") (pin "3") (pinfunction "OUTPUT_3") (pintype "output"))
    )
    (net (code "16") (name "CS1") (class "Default")
      (node (ref "SJ1") (pin "1") (pinfunction "1_1") (pintype "passive"))
      (node (ref "X1") (pin "7") (pinfunction "KL_7") (pintype "passive"))
    )
    (net (code "17") (name "CS2") (class "Default")
      (node (ref "SJ2") (pin "1") (pinfunction "1_1") (pintype "passive"))
      (node (ref "X1") (pin "9") (pinfunction "KL_9") (pintype "passive"))
    )
    (net (code "18") (name "CS3") (class "Default")
      (node (ref "SJ3") (pin "1") (pinfunction "1_1") (pintype "passive"))
      (node (ref "X1") (pin "10") (pinfunction "KL_10") (pintype "passive"))
    )
    (net (code "19") (name "CS_TMC") (class "Default")
      (node (ref "SJ1") (pin "2") (pinfunction "2_2") (pintype "passive"))
      (node (ref "SJ2") (pin "2") (pinfunction "2_2") (pintype "passive"))
      (node (ref "SJ3") (pin "2") (pinfunction "2_2") (pintype "passive"))
      (node (ref "U1") (pin "6") (pinfunction "SPI_NSCS_6") (pintype "input"))
    )
    (net (code "20") (name "C_HS_A") (class "Default")
      (node (ref "U1") (pin "39") (pinfunction "PWM_UX1_H_39") (pintype "output"))
      (node (ref "U5") (pin "2") (pinfunction "HI_2") (pintype "input"))
    )
    (net (code "21") (name "C_HS_B") (class "Default")
      (node (ref "U1") (pin "41") (pinfunction "PWM_VX2_H_41") (pintype "output"))
      (node (ref "U4") (pin "2") (pinfunction "HI_2") (pintype "input"))
    )
    (net (code "22") (name "C_HS_C") (class "Default")
      (node (ref "U1") (pin "46") (pinfunction "PWM_WY1_H_46") (pintype "output"))
      (node (ref "U3") (pin "2") (pinfunction "HI_2") (pintype "input"))
    )
    (net (code "23") (name "C_HS_D") (class "Default")
      (node (ref "U1") (pin "48") (pinfunction "PWM_Y2_H_48") (pintype "output"))
      (node (ref "U2") (pin "2") (pinfunction "HI_2") (pintype "input"))
    )
    (net (code "24") (name "C_LS_A") (class "Default")
      (node (ref "U1") (pin "40") (pinfunction "PWM_UX1_L_40") (pintype "output"))
      (node (ref "U5") (pin "3") (pinfunction "LI_3") (pintype "input"))
    )
    (net (code "25") (name "C_LS_B") (class "Default")
      (node (ref "U1") (pin "42") (pinfunction "PWM_VX2_L_42") (pintype "output"))
      (node (ref "U4") (pin "3") (pinfunction "LI_3") (pintype "input"))
    )
    (net (code "26") (name "C_LS_C") (class "Default")
      (node (ref "U1") (pin "47") (pinfunction "PWM_WY1_L_47") (pintype "output"))
      (node (ref "U3") (pin "3") (pinfunction "LI_3") (pintype "input"))
    )
    (net (code "27") (name "C_LS_D") (class "Default")
      (node (ref "U1") (pin "49") (pinfunction "PWM_Y2_L_49") (pintype "output"))
      (node (ref "U2") (pin "3") (pinfunction "LI_3") (pintype "input"))
    )
    (net (code "28") (name "DIR") (class "Default")
      (node (ref "JP10") (pin "3") (pinfunction "3_3") (pintype "passive"))
      (node (ref "U1") (pin "56") (pinfunction "DIR_56") (pintype "input"))
    )
    (net (code "29") (name "ENABLE") (class "Default")
      (node (ref "JP7") (pin "2") (pinfunction "2_2") (pintype "passive"))
      (node (ref "R31") (pin "1") (pinfunction "1_1") (pintype "passive"))
      (node (ref "U1") (pin "55") (pinfunction "ENI_55") (pintype "input"))
    )
    (net (code "30") (name "ENC2_A") (class "Default")
      (node (ref "JP9") (pin "2") (pinfunction "2_2") (pintype "passive"))
      (node (ref "U1") (pin "64") (pinfunction "ENC2_A_64") (pintype "input"))
    )
    (net (code "31") (name "ENC2_B") (class "Default")
      (node (ref "JP9") (pin "4") (pinfunction "4_4") (pintype "passive"))
      (node (ref "U1") (pin "65") (pinfunction "ENC2_B_65") (pintype "input"))
    )
    (net (code "32") (name "ENC2_Z") (class "Default")
      (node (ref "JP9") (pin "6") (pinfunction "6_6") (pintype "passive"))
      (node (ref "U1") (pin "66") (pinfunction "ENC2_N_66") (pintype "input"))
    )
    (net (code "33") (name "ENC_A") (class "Default")
      (node (ref "U1") (pin "35") (pinfunction "ENC_A_35") (pintype "input"))
      (node (ref "U18") (pin "P$2") (pinfunction "3Y_P$2") (pintype "bidirectional"))
    )
    (net (code "34") (name "ENC_A_5V") (class "Default")
      (node (ref "C36") (pin "2") (pinfunction "2_2") (pintype "passive"))
      (node (ref "R46") (pin "1") (pinfunction "1_1") (pintype "passive"))
      (node (ref "U18") (pin "P$6") (pinfunction "3A_P$6") (pintype "bidirectional"))
    )
    (net (code "35") (name "ENC_B") (class "Default")
      (node (ref "U1") (pin "34") (pinfunction "ENC_B_34") (pintype "input"))
      (node (ref "U18") (pin "P$5") (pinfunction "2Y_P$5") (pintype "bidirectional"))
    )
    (net (code "36") (name "ENC_B_5V") (class "Default")
      (node (ref "C34") (pin "2") (pinfunction "2_2") (pintype "passive"))
      (node (ref "R45") (pin "1") (pinfunction "1_1") (pintype "passive"))
      (node (ref "U18") (pin "P$3") (pinfunction "2A_P$3") (pintype "bidirectional"))
    )
    (net (code "37") (name "ENC_Z") (class "Default")
      (node (ref "U1") (pin "33") (pinfunction "ENC_N_33") (pintype "input"))
      (node (ref "U18") (pin "P$7") (pinfunction "1Y_P$7") (pintype "bidirectional"))
    )
    (net (code "38") (name "ENC_Z_5V") (class "Default")
      (node (ref "C32") (pin "2") (pinfunction "2_2") (pintype "passive"))
      (node (ref "R44") (pin "1") (pinfunction "1_1") (pintype "passive"))
      (node (ref "U18") (pin "P$1") (pinfunction "1A_P$1") (pintype "bidirectional"))
    )
    (net (code "39") (name "ENO") (class "Default")
      (node (ref "U1") (pin "32") (pinfunction "ENO_32") (pintype "output"))
    )
    (net (code "40") (name "FLAG") (class "Default")
      (node (ref "D1") (pin "C") (pinfunction "C_C") (pintype "passive"))
      (node (ref "R4") (pin "2") (pinfunction "2_2") (pintype "passive"))
      (node (ref "X1") (pin "11") (pinfunction "KL_11") (pintype "passive"))
    )
    (net (code "41") (name "GND") (class "Default")
      (node (ref "C1") (pin "1") (pinfunction "1_1") (pintype "passive"))
      (node (ref "C10") (pin "1") (pinfunction "1_1") (pintype "passive"))
      (node (ref "C11") (pin "-") (pinfunction "-_-") (pintype "passive"))
      (node (ref "C12") (pin "-") (pinfunction "-_-") (pintype "passive"))
      (node (ref "C13") (pin "2") (pinfunction "2_2") (pintype "passive"))
      (node (ref "C14") (pin "2") (pinfunction "2_2") (pintype "passive"))
      (node (ref "C15") (pin "2") (pinfunction "2_2") (pintype "passive"))
      (node (ref "C16") (pin "2") (pinfunction "2_2") (pintype "passive"))
      (node (ref "C17") (pin "2") (pinfunction "2_2") (pintype "passive"))
      (node (ref "C18") (pin "2") (pinfunction "2_2") (pintype "passive"))
      (node (ref "C19") (pin "2") (pinfunction "2_2") (pintype "passive"))
      (node (ref "C2") (pin "1") (pinfunction "1_1") (pintype "passive"))
      (node (ref "C20") (pin "2") (pinfunction "2_2") (pintype "passive"))
      (node (ref "C25") (pin "2") (pinfunction "2_2") (pintype "passive"))
      (node (ref "C26") (pin "2") (pinfunction "2_2") (pintype "passive"))
      (node (ref "C27") (pin "2") (pinfunction "2_2") (pintype "passive"))
      (node (ref "C28") (pin "2") (pinfunction "2_2") (pintype "passive"))
      (node (ref "C29") (pin "-") (pinfunction "-_-") (pintype "passive"))
      (node (ref "C3") (pin "1") (pinfunction "1_1") (pintype "passive"))
      (node (ref "C30") (pin "1") (pinfunction "1_1") (pintype "passive"))
      (node (ref "C31") (pin "1") (pinfunction "1_1") (pintype "passive"))
      (node (ref "C32") (pin "1") (pinfunction "1_1") (pintype "passive"))
      (node (ref "C33") (pin "1") (pinfunction "1_1") (pintype "passive"))
      (node (ref "C34") (pin "1") (pinfunction "1_1") (pintype "passive"))
      (node (ref "C35") (pin "1") (pinfunction "1_1") (pintype "passive"))
      (node (ref "C36") (pin "1") (pinfunction "1_1") (pintype "passive"))
      (node (ref "C37") (pin "1") (pinfunction "1_1") (pintype "passive"))
      (node (ref "C38") (pin "2") (pinfunction "2_2") (pintype "passive"))
      (node (ref "C4") (pin "1") (pinfunction "1_1") (pintype "passive"))
      (node (ref "C40") (pin "2") (pinfunction "2_2") (pintype "passive"))
      (node (ref "C41") (pin "1") (pinfunction "1_1") (pintype "passive"))
      (node (ref "C43") (pin "1") (pinfunction "1_1") (pintype "passive"))
      (node (ref "C44") (pin "2") (pinfunction "2_2") (pintype "passive"))
      (node (ref "C45") (pin "2") (pinfunction "2_2") (pintype "passive"))
      (node (ref "C5") (pin "1") (pinfunction "1_1") (pintype "passive"))
      (node (ref "C6") (pin "1") (pinfunction "1_1") (pintype "passive"))
      (node (ref "C7") (pin "1") (pinfunction "1_1") (pintype "passive"))
      (node (ref "C8") (pin "1") (pinfunction "1_1") (pintype "passive"))
      (node (ref "C9") (pin "1") (pinfunction "1_1") (pintype "passive"))
      (node (ref "D12") (pin "A") (pinfunction "A_A") (pintype "passive"))
      (node (ref "D13") (pin "A") (pinfunction "A_A") (pintype "passive"))
      (node (ref "D15") (pin "A") (pinfunction "A_A") (pintype "passive"))
      (node (ref "H1") (pin "B3,0") (pinfunction "MOUNT_B3,0") (pintype "passive"))
      (node (ref "H2") (pin "B3,0") (pinfunction "MOUNT_B3,0") (pintype "passive"))
      (node (ref "H3") (pin "B3,0") (pinfunction "MOUNT_B3,0") (pintype "passive"))
      (node (ref "H4") (pin "B3,0") (pinfunction "MOUNT_B3,0") (pintype "passive"))
      (node (ref "H5") (pin "B3,0") (pinfunction "MOUNT_B3,0") (pintype "passive"))
      (node (ref "H6") (pin "B3,0") (pinfunction "MOUNT_B3,0") (pintype "passive"))
      (node (ref "JP11") (pin "5") (pinfunction "5_5") (pintype "passive"))
      (node (ref "JP12") (pin "5") (pinfunction "5_5") (pintype "passive"))
      (node (ref "JP2") (pin "1") (pinfunction "1_1") (pintype "passive"))
      (node (ref "JP6") (pin "3") (pinfunction "3_3") (pintype "passive"))
      (node (ref "JP7") (pin "1") (pinfunction "1_1") (pintype "passive"))
      (node (ref "LED1") (pin "C") (pinfunction "C_C") (pintype "passive"))
      (node (ref "R14") (pin "1") (pinfunction "1_1") (pintype "passive"))
      (node (ref "R16") (pin "1") (pinfunction "1_1") (pintype "passive"))
      (node (ref "R17") (pin "1") (pinfunction "1_1") (pintype "passive"))
      (node (ref "R19") (pin "1") (pinfunction "1_1") (pintype "passive"))
      (node (ref "R2") (pin "1") (pinfunction "1_1") (pintype "passive"))
      (node (ref "R20") (pin "1") (pinfunction "1_1") (pintype "passive"))
      (node (ref "R25") (pin "1") (pinfunction "1_1") (pintype "passive"))
      (node (ref "R26") (pin "1") (pinfunction "1_1") (pintype "passive"))
      (node (ref "R28") (pin "1") (pinfunction "1_1") (pintype "passive"))
      (node (ref "R30") (pin "1") (pinfunction "1_1") (pintype "passive"))
      (node (ref "R33") (pin "1") (pinfunction "1_1") (pintype "passive"))
      (node (ref "R4") (pin "1") (pinfunction "1_1") (pintype "passive"))
      (node (ref "R48") (pin "2") (pinfunction "2_2") (pintype "passive"))
      (node (ref "R50") (pin "1") (pinfunction "1_1") (pintype "passive"))
      (node (ref "R51") (pin "1") (pinfunction "1_1") (pintype "passive"))
      (node (ref "U1") (pin "14") (pinfunction "GNDIO2_14") (pintype "power_in"))
      (node (ref "U1") (pin "24") (pinfunction "GNDA_24") (pintype "power_in"))
      (node (ref "U1") (pin "3") (pinfunction "GNDIO1_3") (pintype "power_in"))
      (node (ref "U1") (pin "44") (pinfunction "GNDIO3_44") (pintype "power_in"))
      (node (ref "U1") (pin "53") (pinfunction "GNDIO4_53") (pintype "power_in"))
      (node (ref "U1") (pin "54") (pinfunction "TEST_54") (pintype "input"))
      (node (ref "U1") (pin "59") (pinfunction "PWM_IDLE_H_59") (pintype "input"))
      (node (ref "U1") (pin "60") (pinfunction "PWM_IDLE_L_60") (pintype "input"))
      (node (ref "U1") (pin "62") (pinfunction "GNDIO5_62") (pintype "power_in"))
      (node (ref "U1") (pin "73") (pinfunction "GNDIO6_73") (pintype "power_in"))
      (node (ref "U1") (pin "77") (pinfunction "GNDIO6_77") (pintype "power_in"))
      (node (ref "U11") (pin "1") (pinfunction "S_1") (pintype "passive"))
      (node (ref "U11") (pin "2") (pinfunction "S_2") (pintype "passive"))
      (node (ref "U11") (pin "3") (pinfunction "S_3") (pintype "passive"))
      (node (ref "U13") (pin "1") (pinfunction "S_1") (pintype "passive"))
      (node (ref "U13") (pin "2") (pinfunction "S_2") (pintype "passive"))
      (node (ref "U13") (pin "3") (pinfunction "S_3") (pintype "passive"))
      (node (ref "U14") (pin "1") (pinfunction "GND_1") (pintype "bidirectional"))
      (node (ref "U14") (pin "4") (pinfunction "GND_4") (pintype "bidirectional"))
      (node (ref "U16") (pin "1") (pinfunction "S_1") (pintype "passive"))
      (node (ref "U16") (pin "2") (pinfunction "S_2") (pintype "passive"))
      (node (ref "U16") (pin "3") (pinfunction "S_3") (pintype "passive"))
      (node (ref "U17") (pin "1") (pinfunction "S_1") (pintype "passive"))
      (node (ref "U17") (pin "2") (pinfunction "S_2") (pintype "passive"))
      (node (ref "U17") (pin "3") (pinfunction "S_3") (pintype "passive"))
      (node (ref "U18") (pin "P$4") (pinfunction "GND_P$4") (pintype "bidirectional"))
      (node (ref "U19") (pin "P$4") (pinfunction "GND_P$4") (pintype "bidirectional"))
      (node (ref "U2") (pin "4") (pinfunction "VSS_4") (pintype "power_in"))
      (node (ref "U2") (pin "9") (pinfunction "EP_9") (pintype "power_in"))
      (node (ref "U20") (pin "2") (pinfunction "GND_2") (pintype "bidirectional"))
      (node (ref "U21") (pin "1") (pinfunction "ADJ_1") (pintype "input"))
      (node (ref "U23") (pin "3") (pinfunction "SGND_3") (pintype "power_in"))
      (node (ref "U23") (pin "6") (pinfunction "GND_6") (pintype "power_in"))
      (node (ref "U24") (pin "2") (pinfunction "GND_2") (pintype "bidirectional"))
      (node (ref "U3") (pin "4") (pinfunction "VSS_4") (pintype "power_in"))
      (node (ref "U3") (pin "9") (pinfunction "EP_9") (pintype "power_in"))
      (node (ref "U4") (pin "4") (pinfunction "VSS_4") (pintype "power_in"))
      (node (ref "U4") (pin "9") (pinfunction "EP_9") (pintype "power_in"))
      (node (ref "U5") (pin "4") (pinfunction "VSS_4") (pintype "power_in"))
      (node (ref "U5") (pin "9") (pinfunction "EP_9") (pintype "power_in"))
      (node (ref "U7") (pin "1") (pinfunction "S_1") (pintype "passive"))
      (node (ref "U7") (pin "2") (pinfunction "S_2") (pintype "passive"))
      (node (ref "U7") (pin "3") (pinfunction "S_3") (pintype "passive"))
      (node (ref "U8") (pin "2") (pinfunction "GND_2") (pintype "bidirectional"))
      (node (ref "U9") (pin "2") (pinfunction "GND_2") (pintype "bidirectional"))
      (node (ref "X1") (pin "1") (pinfunction "KL_1") (pintype "passive"))
      (node (ref "X2") (pin "1") (pinfunction "1_1") (pintype "passive"))
      (node (ref "Y1") (pin "2") (pinfunction "GND_2") (pintype "power_in"))
    )
    (net (code "42") (name "GPIO0") (class "Default")
      (node (ref "JP8") (pin "1") (pinfunction "1_1") (pintype "passive"))
      (node (ref "U1") (pin "70") (pinfunction "GPIO0/ADC_I0_MCD_70") (pintype "bidirectional"))
    )
    (net (code "43") (name "GPIO1") (class "Default")
      (node (ref "JP8") (pin "2") (pinfunction "2_2") (pintype "passive"))
      (node (ref "U1") (pin "71") (pinfunction "GPIO1/ADC_I1_MCD_71") (pintype "bidirectional"))
    )
    (net (code "44") (name "GPIO2") (class "Default")
      (node (ref "JP8") (pin "3") (pinfunction "3_3") (pintype "passive"))
      (node (ref "U1") (pin "74") (pinfunction "GPIO2/ADC_VM_MCD_74") (pintype "bidirectional"))
    )
    (net (code "45") (name "GPIO3") (class "Default")
      (node (ref "JP8") (pin "4") (pinfunction "4_4") (pintype "passive"))
      (node (ref "U1") (pin "75") (pinfunction "GPIO3/AGPI_A_MCD/DBGSPI_NSCS_75") (pintype "bidirectional"))
    )
    (net (code "46") (name "GPIO4") (class "Default")
      (node (ref "JP8") (pin "5") (pinfunction "5_5") (pintype "passive"))
      (node (ref "U1") (pin "76") (pinfunction "GPIO4/AGPI_B_MCD/DBGSPI_SCK_76") (pintype "bidirectional"))
    )
    (net (code "47") (name "GPIO5") (class "Default")
      (node (ref "JP8") (pin "6") (pinfunction "6_6") (pintype "passive"))
      (node (ref "U1") (pin "1") (pinfunction "GPIO5/AENC_UX_MCD/DBGSPI_MOSI_1") (pintype "bidirectional"))
    )
    (net (code "48") (name "GPIO6") (class "Default")
      (node (ref "JP8") (pin "7") (pinfunction "7_7") (pintype "passive"))
      (node (ref "U1") (pin "4") (pinfunction "GPIO6/AENC_VN_MCD/DBGSPI_MISO_4") (pintype "bidirectional"))
    )
    (net (code "49") (name "GPIO7") (class "Default")
      (node (ref "JP8") (pin "8") (pinfunction "8_8") (pintype "passive"))
      (node (ref "U1") (pin "5") (pinfunction "GPIO7/AENC_WY_MCD/DBGSPI_TRG_5") (pintype "bidirectional"))
    )
    (net (code "50") (name "G_HS_A") (class "Default")
      (node (ref "D6") (pin "C") (pinfunction "C_C") (pintype "passive"))
      (node (ref "R11") (pin "1") (pinfunction "1_1") (pintype "passive"))
      (node (ref "U6") (pin "4") (pinfunction "G_4") (pintype "passive"))
    )
    (net (code "51") (name "G_HS_B") (class "Default")
      (node (ref "D7") (pin "C") (pinfunction "C_C") (pintype "passive"))
      (node (ref "R9") (pin "1") (pinfunction "1_1") (pintype "passive"))
      (node (ref "U10") (pin "4") (pinfunction "G_4") (pintype "passive"))
    )
    (net (code "52") (name "G_HS_C") (class "Default")
      (node (ref "D8") (pin "C") (pinfunction "C_C") (pintype "passive"))
      (node (ref "R7") (pin "1") (pinfunction "1_1") (pintype "passive"))
      (node (ref "U12") (pin "4") (pinfunction "G_4") (pintype "passive"))
    )
    (net (code "53") (name "G_HS_D") (class "Default")
      (node (ref "D10") (pin "C") (pinfunction "C_C") (pintype "passive"))
      (node (ref "R5") (pin "1") (pinfunction "1_1") (pintype "passive"))
      (node (ref "U15") (pin "4") (pinfunction "G_4") (pintype "passive"))
    )
    (net (code "54") (name "G_LS_A") (class "Default")
      (node (ref "R12") (pin "1") (pinfunction "1_1") (pintype "passive"))
      (node (ref "R17") (pin "2") (pinfunction "2_2") (pintype "passive"))
      (node (ref "U7") (pin "4") (pinfunction "G_4") (pintype "passive"))
    )
    (net (code "55") (name "G_LS_B") (class "Default")
      (node (ref "R10") (pin "1") (pinfunction "1_1") (pintype "passive"))
      (node (ref "R20") (pin "2") (pinfunction "2_2") (pintype "passive"))
      (node (ref "U11") (pin "4") (pinfunction "G_4") (pintype "passive"))
    )
    (net (code "56") (name "G_LS_C") (class "Default")
      (node (ref "R25") (pin "2") (pinfunction "2_2") (pintype "passive"))
      (node (ref "R8") (pin "1") (pinfunction "1_1") (pintype "passive"))
      (node (ref "U13") (pin "4") (pinfunction "G_4") (pintype "passive"))
    )
    (net (code "57") (name "G_LS_D") (class "Default")
      (node (ref "R28") (pin "2") (pinfunction "2_2") (pintype "passive"))
      (node (ref "R6") (pin "1") (pinfunction "1_1") (pintype "passive"))
      (node (ref "U16") (pin "4") (pinfunction "G_4") (pintype "passive"))
    )
    (net (code "58") (name "HALL_UX") (class "Default")
      (node (ref "U1") (pin "38") (pinfunction "HALL_UX_38") (pintype "input"))
      (node (ref "U19") (pin "P$2") (pinfunction "3Y_P$2") (pintype "bidirectional"))
    )
    (net (code "59") (name "HALL_UX_5V") (class "Default")
      (node (ref "C33") (pin "2") (pinfunction "2_2") (pintype "passive"))
      (node (ref "R41") (pin "1") (pinfunction "1_1") (pintype "passive"))
      (node (ref "U19") (pin "P$6") (pinfunction "3A_P$6") (pintype "bidirectional"))
    )
    (net (code "60") (name "HALL_V") (class "Default")
      (node (ref "U1") (pin "37") (pinfunction "HALL_V_37") (pintype "input"))
      (node (ref "U19") (pin "P$5") (pinfunction "2Y_P$5") (pintype "bidirectional"))
    )
    (net (code "61") (name "HALL_V_5V") (class "Default")
      (node (ref "C35") (pin "2") (pinfunction "2_2") (pintype "passive"))
      (node (ref "R42") (pin "1") (pinfunction "1_1") (pintype "passive"))
      (node (ref "U19") (pin "P$3") (pinfunction "2A_P$3") (pintype "bidirectional"))
    )
    (net (code "62") (name "HALL_WY") (class "Default")
      (node (ref "U1") (pin "36") (pinfunction "HALL_WY_36") (pintype "input"))
      (node (ref "U19") (pin "P$7") (pinfunction "1Y_P$7") (pintype "bidirectional"))
    )
    (net (code "63") (name "HALL_WY_5V") (class "Default")
      (node (ref "C37") (pin "2") (pinfunction "2_2") (pintype "passive"))
      (node (ref "R43") (pin "1") (pinfunction "1_1") (pintype "passive"))
      (node (ref "U19") (pin "P$1") (pinfunction "1A_P$1") (pintype "bidirectional"))
    )
    (net (code "64") (name "INPUT_GATE") (class "Default")
      (node (ref "U20") (pin "5") (pinfunction "GATE_5") (pintype "bidirectional"))
      (node (ref "U22") (pin "4") (pinfunction "G_4") (pintype "passive"))
    )
    (net (code "65") (name "MISO") (class "Default")
      (node (ref "U1") (pin "9") (pinfunction "SPI_MISO_9") (pintype "output"))
      (node (ref "X1") (pin "6") (pinfunction "KL_6") (pintype "passive"))
    )
    (net (code "66") (name "MOSI") (class "Default")
      (node (ref "U1") (pin "8") (pinfunction "SPI_MOSI_8") (pintype "input"))
      (node (ref "X1") (pin "5") (pinfunction "KL_5") (pintype "passive"))
    )
    (net (code "67") (name "MOT_A") (class "Default")
      (node (ref "C24") (pin "2") (pinfunction "2_2") (pintype "passive"))
      (node (ref "D6") (pin "A") (pinfunction "A_A") (pintype "passive"))
      (node (ref "R22") (pin "2") (pinfunction "2_2") (pintype "passive"))
      (node (ref "U5") (pin "6") (pinfunction "HS_6") (pintype "input"))
      (node (ref "U6") (pin "1") (pinfunction "S_1") (pintype "passive"))
      (node (ref "U6") (pin "2") (pinfunction "S_2") (pintype "passive"))
      (node (ref "U6") (pin "3") (pinfunction "S_3") (pintype "passive"))
      (node (ref "U7") (pin "5") (pinfunction "D_5") (pintype "passive"))
      (node (ref "U8") (pin "8") (pinfunction "IN+_8") (pintype "bidirectional"))
    )
    (net (code "68") (name "MOT_A_OUT") (class "Default")
      (node (ref "R22") (pin "1") (pinfunction "1_1") (pintype "passive"))
      (node (ref "U8") (pin "1") (pinfunction "IN-_1") (pintype "bidirectional"))
      (node (ref "X3") (pin "1") (pinfunction "1_1") (pintype "passive"))
    )
    (net (code "69") (name "MOT_B") (class "Default")
      (node (ref "C23") (pin "2") (pinfunction "2_2") (pintype "passive"))
      (node (ref "D7") (pin "A") (pinfunction "A_A") (pintype "passive"))
      (node (ref "U10") (pin "1") (pinfunction "S_1") (pintype "passive"))
      (node (ref "U10") (pin "2") (pinfunction "S_2") (pintype "passive"))
      (node (ref "U10") (pin "3") (pinfunction "S_3") (pintype "passive"))
      (node (ref "U11") (pin "5") (pinfunction "D_5") (pintype "passive"))
      (node (ref "U4") (pin "6") (pinfunction "HS_6") (pintype "input"))
      (node (ref "X3") (pin "2") (pinfunction "1_2") (pintype "passive"))
    )
    (net (code "70") (name "MOT_C") (class "Default")
      (node (ref "C22") (pin "2") (pinfunction "2_2") (pintype "passive"))
      (node (ref "D8") (pin "A") (pinfunction "A_A") (pintype "passive"))
      (node (ref "R21") (pin "2") (pinfunction "2_2") (pintype "passive"))
      (node (ref "U12") (pin "1") (pinfunction "S_1") (pintype "passive"))
      (node (ref "U12") (pin "2") (pinfunction "S_2") (pintype "passive"))
      (node (ref "U12") (pin "3") (pinfunction "S_3") (pintype "passive"))
      (node (ref "U13") (pin "5") (pinfunction "D_5") (pintype "passive"))
      (node (ref "U3") (pin "6") (pinfunction "HS_6") (pintype "input"))
      (node (ref "U9") (pin "8") (pinfunction "IN+_8") (pintype "bidirectional"))
    )
    (net (code "71") (name "MOT_C_OUT") (class "Default")
      (node (ref "R21") (pin "1") (pinfunction "1_1") (pintype "passive"))
      (node (ref "U9") (pin "1") (pinfunction "IN-_1") (pintype "bidirectional"))
      (node (ref "X3") (pin "3") (pinfunction "1_3") (pintype "passive"))
    )
    (net (code "72") (name "MOT_D") (class "Default")
      (node (ref "C21") (pin "2") (pinfunction "2_2") (pintype "passive"))
      (node (ref "D10") (pin "A") (pinfunction "A_A") (pintype "passive"))
      (node (ref "U15") (pin "1") (pinfunction "S_1") (pintype "passive"))
      (node (ref "U15") (pin "2") (pinfunction "S_2") (pintype "passive"))
      (node (ref "U15") (pin "3") (pinfunction "S_3") (pintype "passive"))
      (node (ref "U16") (pin "5") (pinfunction "D_5") (pintype "passive"))
      (node (ref "U2") (pin "6") (pinfunction "HS_6") (pintype "input"))
      (node (ref "X3") (pin "4") (pinfunction "1_4") (pintype "passive"))
    )
    (net (code "73") (name "Net-(JP3-Pad2)") (class "Default")
      (node (ref "JP3") (pin "2") (pinfunction "2_2") (pintype "passive"))
      (node (ref "JP3") (pin "4") (pinfunction "4_4") (pintype "passive"))
      (node (ref "JP3") (pin "6") (pinfunction "6_6") (pintype "passive"))
      (node (ref "R32") (pin "1") (pinfunction "1_1") (pintype "passive"))
      (node (ref "R33") (pin "2") (pinfunction "2_2") (pintype "passive"))
    )
    (net (code "74") (name "Net-(JP11-Pad2)") (class "Default")
      (node (ref "JP11") (pin "2") (pinfunction "2_2") (pintype "passive"))
      (node (ref "R35") (pin "1") (pinfunction "1_1") (pintype "passive"))
      (node (ref "R44") (pin "2") (pinfunction "2_2") (pintype "passive"))
    )
    (net (code "75") (name "Net-(JP11-Pad3)") (class "Default")
      (node (ref "JP11") (pin "3") (pinfunction "3_3") (pintype "passive"))
      (node (ref "R36") (pin "1") (pinfunction "1_1") (pintype "passive"))
      (node (ref "R45") (pin "2") (pinfunction "2_2") (pintype "passive"))
    )
    (net (code "76") (name "Net-(JP11-Pad4)") (class "Default")
      (node (ref "JP11") (pin "4") (pinfunction "4_4") (pintype "passive"))
      (node (ref "R38") (pin "1") (pinfunction "1_1") (pintype "passive"))
      (node (ref "R46") (pin "2") (pinfunction "2_2") (pintype "passive"))
    )
    (net (code "77") (name "Net-(JP12-Pad2)") (class "Default")
      (node (ref "JP12") (pin "2") (pinfunction "2_2") (pintype "passive"))
      (node (ref "R40") (pin "1") (pinfunction "1_1") (pintype "passive"))
      (node (ref "R43") (pin "2") (pinfunction "2_2") (pintype "passive"))
    )
    (net (code "78") (name "Net-(JP12-Pad3)") (class "Default")
      (node (ref "JP12") (pin "3") (pinfunction "3_3") (pintype "passive"))
      (node (ref "R39") (pin "1") (pinfunction "1_1") (pintype "passive"))
      (node (ref "R42") (pin "2") (pinfunction "2_2") (pintype "passive"))
    )
    (net (code "79") (name "Net-(JP12-Pad4)") (class "Default")
      (node (ref "JP12") (pin "4") (pinfunction "4_4") (pintype "passive"))
      (node (ref "R37") (pin "1") (pinfunction "1_1") (pintype "passive"))
      (node (ref "R41") (pin "2") (pinfunction "2_2") (pintype "passive"))
    )
    (net (code "80") (name "Net-(LED1-PadA)") (class "Default")
      (node (ref "LED1") (pin "A") (pinfunction "A_A") (pintype "passive"))
      (node (ref "R34") (pin "1") (pinfunction "1_1") (pintype "passive"))
    )
    (net (code "81") (name "Net-(U1B-STATUS)") (class "Default")
      (node (ref "D1") (pin "A") (pinfunction "A_A") (pintype "passive"))
      (node (ref "U1") (pin "12") (pinfunction "STATUS_12") (pintype "output"))
    )
    (net (code "82") (name "Net-(U1B-VCCCORE1)") (class "Default")
      (node (ref "C3") (pin "2") (pinfunction "2_2") (pintype "passive"))
      (node (ref "C5") (pin "2") (pinfunction "2_2") (pintype "passive"))
      (node (ref "C6") (pin "2") (pinfunction "2_2") (pintype "passive"))
      (node (ref "U1") (pin "15") (pinfunction "VCCCORE1_15") (pintype "power_in"))
      (node (ref "U1") (pin "45") (pinfunction "VCCCORE2_45") (pintype "power_in"))
      (node (ref "U1") (pin "63") (pinfunction "VCCCORE3_63") (pintype "power_in"))
    )
    (net (code "83") (name "Net-(U2-HB)") (class "Default")
      (node (ref "C21") (pin "1") (pinfunction "1_1") (pintype "passive"))
      (node (ref "D2") (pin "C") (pinfunction "C_C") (pintype "passive"))
      (node (ref "U2") (pin "8") (pinfunction "HB_8") (pintype "input"))
    )
    (net (code "84") (name "Net-(U2-HO)") (class "Default")
      (node (ref "R5") (pin "2") (pinfunction "2_2") (pintype "passive"))
      (node (ref "U2") (pin "7") (pinfunction "HO_7") (pintype "output"))
    )
    (net (code "85") (name "Net-(U2-LO)") (class "Default")
      (node (ref "R6") (pin "2") (pinfunction "2_2") (pintype "passive"))
      (node (ref "U2") (pin "5") (pinfunction "LO_5") (pintype "output"))
    )
    (net (code "86") (name "Net-(U3-HB)") (class "Default")
      (node (ref "C22") (pin "1") (pinfunction "1_1") (pintype "passive"))
      (node (ref "D3") (pin "C") (pinfunction "C_C") (pintype "passive"))
      (node (ref "U3") (pin "8") (pinfunction "HB_8") (pintype "input"))
    )
    (net (code "87") (name "Net-(U3-HO)") (class "Default")
      (node (ref "R7") (pin "2") (pinfunction "2_2") (pintype "passive"))
      (node (ref "U3") (pin "7") (pinfunction "HO_7") (pintype "output"))
    )
    (net (code "88") (name "Net-(U3-LO)") (class "Default")
      (node (ref "R8") (pin "2") (pinfunction "2_2") (pintype "passive"))
      (node (ref "U3") (pin "5") (pinfunction "LO_5") (pintype "output"))
    )
    (net (code "89") (name "Net-(U4-HB)") (class "Default")
      (node (ref "C23") (pin "1") (pinfunction "1_1") (pintype "passive"))
      (node (ref "D4") (pin "C") (pinfunction "C_C") (pintype "passive"))
      (node (ref "U4") (pin "8") (pinfunction "HB_8") (pintype "input"))
    )
    (net (code "90") (name "Net-(U4-HO)") (class "Default")
      (node (ref "R9") (pin "2") (pinfunction "2_2") (pintype "passive"))
      (node (ref "U4") (pin "7") (pinfunction "HO_7") (pintype "output"))
    )
    (net (code "91") (name "Net-(U4-LO)") (class "Default")
      (node (ref "R10") (pin "2") (pinfunction "2_2") (pintype "passive"))
      (node (ref "U4") (pin "5") (pinfunction "LO_5") (pintype "output"))
    )
    (net (code "92") (name "Net-(U5-HB)") (class "Default")
      (node (ref "C24") (pin "1") (pinfunction "1_1") (pintype "passive"))
      (node (ref "D5") (pin "C") (pinfunction "C_C") (pintype "passive"))
      (node (ref "U5") (pin "8") (pinfunction "HB_8") (pintype "input"))
    )
    (net (code "93") (name "Net-(U5-HO)") (class "Default")
      (node (ref "R11") (pin "2") (pinfunction "2_2") (pintype "passive"))
      (node (ref "U5") (pin "7") (pinfunction "HO_7") (pintype "output"))
    )
    (net (code "94") (name "Net-(U5-LO)") (class "Default")
      (node (ref "R12") (pin "2") (pinfunction "2_2") (pintype "passive"))
      (node (ref "U5") (pin "5") (pinfunction "LO_5") (pintype "output"))
    )
    (net (code "95") (name "Net-(U8-OUT)") (class "Default")
      (node (ref "R23") (pin "2") (pinfunction "2_2") (pintype "passive"))
      (node (ref "U8") (pin "5") (pinfunction "OUT_5") (pintype "bidirectional"))
    )
    (net (code "96") (name "Net-(U9-OUT)") (class "Default")
      (node (ref "R24") (pin "2") (pinfunction "2_2") (pintype "passive"))
      (node (ref "U9") (pin "5") (pinfunction "OUT_5") (pintype "bidirectional"))
    )
    (net (code "97") (name "Net-(U20-VCAP)") (class "Default")
      (node (ref "C39") (pin "1") (pinfunction "1_1") (pintype "passive"))
      (node (ref "U20") (pin "1") (pinfunction "VCAP_1") (pintype "bidirectional"))
    )
    (net (code "98") (name "Net-(U23-BST)") (class "Default")
      (node (ref "C42") (pin "1") (pinfunction "1_1") (pintype "passive"))
      (node (ref "U23") (pin "1") (pinfunction "BST_1") (pintype "passive"))
    )
    (net (code "99") (name "Net-(U23-LX)") (class "Default")
      (node (ref "C42") (pin "2") (pinfunction "2_2") (pintype "passive"))
      (node (ref "D12") (pin "C") (pinfunction "C_C") (pintype "passive"))
      (node (ref "L1") (pin "1") (pinfunction "1_1") (pintype "passive"))
      (node (ref "U23") (pin "8") (pinfunction "LX_8") (pintype "passive"))
    )
    (net (code "100") (name "Net-(U23-ON{slash}~{OFF})") (class "Default")
      (node (ref "R47") (pin "1") (pinfunction "1_1") (pintype "passive"))
      (node (ref "R48") (pin "1") (pinfunction "1_1") (pintype "passive"))
      (node (ref "U23") (pin "5") (pinfunction "ON/~{OFF}_5") (pintype "input"))
    )
    (net (code "101") (name "Net-(U23-VD)") (class "Default")
      (node (ref "C41") (pin "2") (pinfunction "2_2") (pintype "passive"))
      (node (ref "U23") (pin "2") (pinfunction "VD_2") (pintype "power_in"))
    )
    (net (code "102") (name "Net-(U24-FB)") (class "Default")
      (node (ref "R49") (pin "1") (pinfunction "1_1") (pintype "passive"))
      (node (ref "R50") (pin "2") (pinfunction "2_2") (pintype "passive"))
      (node (ref "U24") (pin "3") (pinfunction "FB_3") (pintype "bidirectional"))
    )
    (net (code "103") (name "Net-(U24-SW)") (class "Default")
      (node (ref "D14") (pin "A") (pinfunction "A_A") (pintype "passive"))
      (node (ref "L2") (pin "2") (pinfunction "2_2") (pintype "passive"))
      (node (ref "U24") (pin "1") (pinfunction "SW_1") (pintype "bidirectional"))
    )
    (net (code "104") (name "Net-(X1H-KL)") (class "Default")
      (node (ref "R31") (pin "2") (pinfunction "2_2") (pintype "passive"))
      (node (ref "X1") (pin "16") (pinfunction "KL_16") (pintype "passive"))
    )
    (net (code "105") (name "Net-(X1I-KL)") (class "Default")
      (node (ref "JP5") (pin "1") (pinfunction "1_1") (pintype "passive"))
      (node (ref "X1") (pin "2") (pinfunction "KL_2") (pintype "passive"))
    )
    (net (code "106") (name "Net-(X1K-KL)") (class "Default")
      (node (ref "SJ4") (pin "1") (pinfunction "1_1") (pintype "passive"))
      (node (ref "X1") (pin "4") (pinfunction "KL_4") (pintype "passive"))
    )
    (net (code "107") (name "PWM_I") (class "Default")
      (node (ref "JP10") (pin "1") (pinfunction "1_1") (pintype "passive"))
      (node (ref "U1") (pin "58") (pinfunction "PWM_I_58") (pintype "input"))
    )
    (net (code "108") (name "REF_H") (class "Default")
      (node (ref "JP9") (pin "3") (pinfunction "3_3") (pintype "passive"))
      (node (ref "U1") (pin "68") (pinfunction "REF_H_68") (pintype "input"))
    )
    (net (code "109") (name "REF_L") (class "Default")
      (node (ref "JP9") (pin "1") (pinfunction "1_1") (pintype "passive"))
      (node (ref "U1") (pin "67") (pinfunction "REF_L_67") (pintype "input"))
    )
    (net (code "110") (name "REF_R") (class "Default")
      (node (ref "JP9") (pin "5") (pinfunction "5_5") (pintype "passive"))
      (node (ref "U1") (pin "69") (pinfunction "REF_R_69") (pintype "input"))
    )
    (net (code "111") (name "RESET") (class "Default")
      (node (ref "R3") (pin "1") (pinfunction "1_1") (pintype "passive"))
      (node (ref "U1") (pin "50") (pinfunction "NRST_50") (pintype "input"))
      (node (ref "X1") (pin "3") (pinfunction "KL_3") (pintype "passive"))
    )
    (net (code "112") (name "RES_FET") (class "Default")
      (node (ref "D11") (pin "A") (pinfunction "A_A") (pintype "passive"))
      (node (ref "D15") (pin "C") (pinfunction "C_C") (pintype "passive"))
      (node (ref "U17") (pin "5") (pinfunction "D_5") (pintype "passive"))
      (node (ref "X2") (pin "4") (pinfunction "1_4") (pintype "passive"))
    )
    (net (code "113") (name "SCK") (class "Default")
      (node (ref "U1") (pin "7") (pinfunction "SPI_SCK_7") (pintype "input"))
      (node (ref "X1") (pin "8") (pinfunction "KL_8") (pintype "passive"))
    )
    (net (code "114") (name "SENSE_A") (class "Default")
      (node (ref "C30") (pin "2") (pinfunction "2_2") (pintype "passive"))
      (node (ref "R23") (pin "1") (pinfunction "1_1") (pintype "passive"))
      (node (ref "U1") (pin "16") (pinfunction "ADC_I0_POS_16") (pintype "input"))
    )
    (net (code "115") (name "SENSE_C") (class "Default")
      (node (ref "C31") (pin "2") (pinfunction "2_2") (pintype "passive"))
      (node (ref "R24") (pin "1") (pinfunction "1_1") (pintype "passive"))
      (node (ref "U1") (pin "18") (pinfunction "ADC_I1_POS_18") (pintype "input"))
    )
    (net (code "116") (name "STEP") (class "Default")
      (node (ref "JP10") (pin "2") (pinfunction "2_2") (pintype "passive"))
      (node (ref "U1") (pin "57") (pinfunction "STP_57") (pintype "input"))
    )
    (net (code "117") (name "UART_RX") (class "Default")
      (node (ref "JP6") (pin "1") (pinfunction "1_1") (pintype "passive"))
      (node (ref "U1") (pin "10") (pinfunction "UART_RXD_10") (pintype "input"))
    )
    (net (code "118") (name "UART_TX") (class "Default")
      (node (ref "JP6") (pin "2") (pinfunction "2_2") (pintype "passive"))
      (node (ref "U1") (pin "11") (pinfunction "UART_TXD_11") (pintype "output"))
    )
    (net (code "119") (name "V+") (class "Default")
      (node (ref "C11") (pin "+") (pinfunction "+_+") (pintype "passive"))
      (node (ref "C12") (pin "+") (pinfunction "+_+") (pintype "passive"))
      (node (ref "C13") (pin "1") (pinfunction "1_1") (pintype "passive"))
      (node (ref "C14") (pin "1") (pinfunction "1_1") (pintype "passive"))
      (node (ref "C15") (pin "1") (pinfunction "1_1") (pintype "passive"))
      (node (ref "C16") (pin "1") (pinfunction "1_1") (pintype "passive"))
      (node (ref "C43") (pin "2") (pinfunction "2_2") (pintype "passive"))
      (node (ref "D11") (pin "C") (pinfunction "C_C") (pintype "passive"))
      (node (ref "R13") (pin "2") (pinfunction "2_2") (pintype "passive"))
      (node (ref "R15") (pin "2") (pinfunction "2_2") (pintype "passive"))
      (node (ref "R47") (pin "2") (pinfunction "2_2") (pintype "passive"))
      (node (ref "U10") (pin "5") (pinfunction "D_5") (pintype "passive"))
      (node (ref "U12") (pin "5") (pinfunction "D_5") (pintype "passive"))
      (node (ref "U15") (pin "5") (pinfunction "D_5") (pintype "passive"))
      (node (ref "U20") (pin "4") (pinfunction "CATHODE_4") (pintype "bidirectional"))
      (node (ref "U22") (pin "5") (pinfunction "D_5") (pintype "passive"))
      (node (ref "U23") (pin "7") (pinfunction "VIN_7") (pintype "power_in"))
      (node (ref "U6") (pin "5") (pinfunction "D_5") (pintype "passive"))
      (node (ref "X2") (pin "2") (pinfunction "1_2") (pintype "passive"))
    )
    (net (code "120") (name "V_EXT") (class "Default")
      (node (ref "R18") (pin "1") (pinfunction "1_1") (pintype "passive"))
      (node (ref "R19") (pin "2") (pinfunction "2_2") (pintype "passive"))
      (node (ref "X1") (pin "13") (pinfunction "KL_13") (pintype "passive"))
    )
    (net (code "121") (name "V_GD") (class "Default")
      (node (ref "C10") (pin "2") (pinfunction "2_2") (pintype "passive"))
      (node (ref "C45") (pin "1") (pinfunction "1_1") (pintype "passive"))
      (node (ref "C7") (pin "2") (pinfunction "2_2") (pintype "passive"))
      (node (ref "C8") (pin "2") (pinfunction "2_2") (pintype "passive"))
      (node (ref "C9") (pin "2") (pinfunction "2_2") (pintype "passive"))
      (node (ref "D14") (pin "C") (pinfunction "C_C") (pintype "passive"))
      (node (ref "D2") (pin "A") (pinfunction "A_A") (pintype "passive"))
      (node (ref "D3") (pin "A") (pinfunction "A_A") (pintype "passive"))
      (node (ref "D4") (pin "A") (pinfunction "A_A") (pintype "passive"))
      (node (ref "D5") (pin "A") (pinfunction "A_A") (pintype "passive"))
      (node (ref "JP4") (pin "1") (pinfunction "1_1") (pintype "passive"))
      (node (ref "R49") (pin "2") (pinfunction "2_2") (pintype "passive"))
      (node (ref "U14") (pin "2") (pinfunction "VDD_2") (pintype "bidirectional"))
      (node (ref "U2") (pin "1") (pinfunction "VDD_1") (pintype "power_in"))
      (node (ref "U3") (pin "1") (pinfunction "VDD_1") (pintype "power_in"))
      (node (ref "U4") (pin "1") (pinfunction "VDD_1") (pintype "power_in"))
      (node (ref "U5") (pin "1") (pinfunction "VDD_1") (pintype "power_in"))
    )
    (net (code "122") (name "V_INT") (class "Default")
      (node (ref "R15") (pin "1") (pinfunction "1_1") (pintype "passive"))
      (node (ref "R16") (pin "2") (pinfunction "2_2") (pintype "passive"))
      (node (ref "X1") (pin "14") (pinfunction "KL_14") (pintype "passive"))
    )
    (net (code "123") (name "V_INT_TMC") (class "Default")
      (node (ref "C25") (pin "1") (pinfunction "1_1") (pintype "passive"))
      (node (ref "R13") (pin "1") (pinfunction "1_1") (pintype "passive"))
      (node (ref "R14") (pin "2") (pinfunction "2_2") (pintype "passive"))
      (node (ref "U1") (pin "20") (pinfunction "ADC_VM_20") (pintype "input"))
    )
    (net (code "124") (name "V_MOT_IN") (class "Default")
      (node (ref "C39") (pin "2") (pinfunction "2_2") (pintype "passive"))
      (node (ref "R18") (pin "2") (pinfunction "2_2") (pintype "passive"))
      (node (ref "U20") (pin "3") (pinfunction "EN_3") (pintype "bidirectional"))
      (node (ref "U20") (pin "6") (pinfunction "ANODE_6") (pintype "bidirectional"))
      (node (ref "U22") (pin "1") (pinfunction "S_1") (pintype "passive"))
      (node (ref "U22") (pin "2") (pinfunction "S_2") (pintype "passive"))
      (node (ref "U22") (pin "3") (pinfunction "S_3") (pintype "passive"))
      (node (ref "X2") (pin "3") (pinfunction "1_3") (pintype "passive"))
    )
    (net (code "125") (name "V_SENSE{slash}2") (class "Default")
      (node (ref "C1") (pin "2") (pinfunction "2_2") (pintype "passive"))
      (node (ref "C2") (pin "2") (pinfunction "2_2") (pintype "passive"))
      (node (ref "R1") (pin "1") (pinfunction "1_1") (pintype "passive"))
      (node (ref "R2") (pin "2") (pinfunction "2_2") (pintype "passive"))
      (node (ref "U1") (pin "17") (pinfunction "ADC_I0_NEG_17") (pintype "input"))
      (node (ref "U1") (pin "19") (pinfunction "ADC_I1_NEG_19") (pintype "input"))
      (node (ref "U8") (pin "3") (pinfunction "REF2_3") (pintype "bidirectional"))
      (node (ref "U8") (pin "7") (pinfunction "REF1_7") (pintype "bidirectional"))
      (node (ref "U9") (pin "3") (pinfunction "REF2_3") (pintype "bidirectional"))
      (node (ref "U9") (pin "7") (pinfunction "REF1_7") (pintype "bidirectional"))
    )
    (net (code "126") (name "unconnected-(X1G-KL-Pad15)") (class "Default")
      (node (ref "X1") (pin "15") (pinfunction "KL_15") (pintype "passive"))
    )
    (net (code "127") (name "unconnected-(Y1-TRI_STATE-Pad1)") (class "Default")
      (node (ref "Y1") (pin "1") (pinfunction "TRI_STATE_1") (pintype "input"))
    )
  )
)
